# module_decoding_b.net
KiCad netlist of a schematic drawn in EAGLE
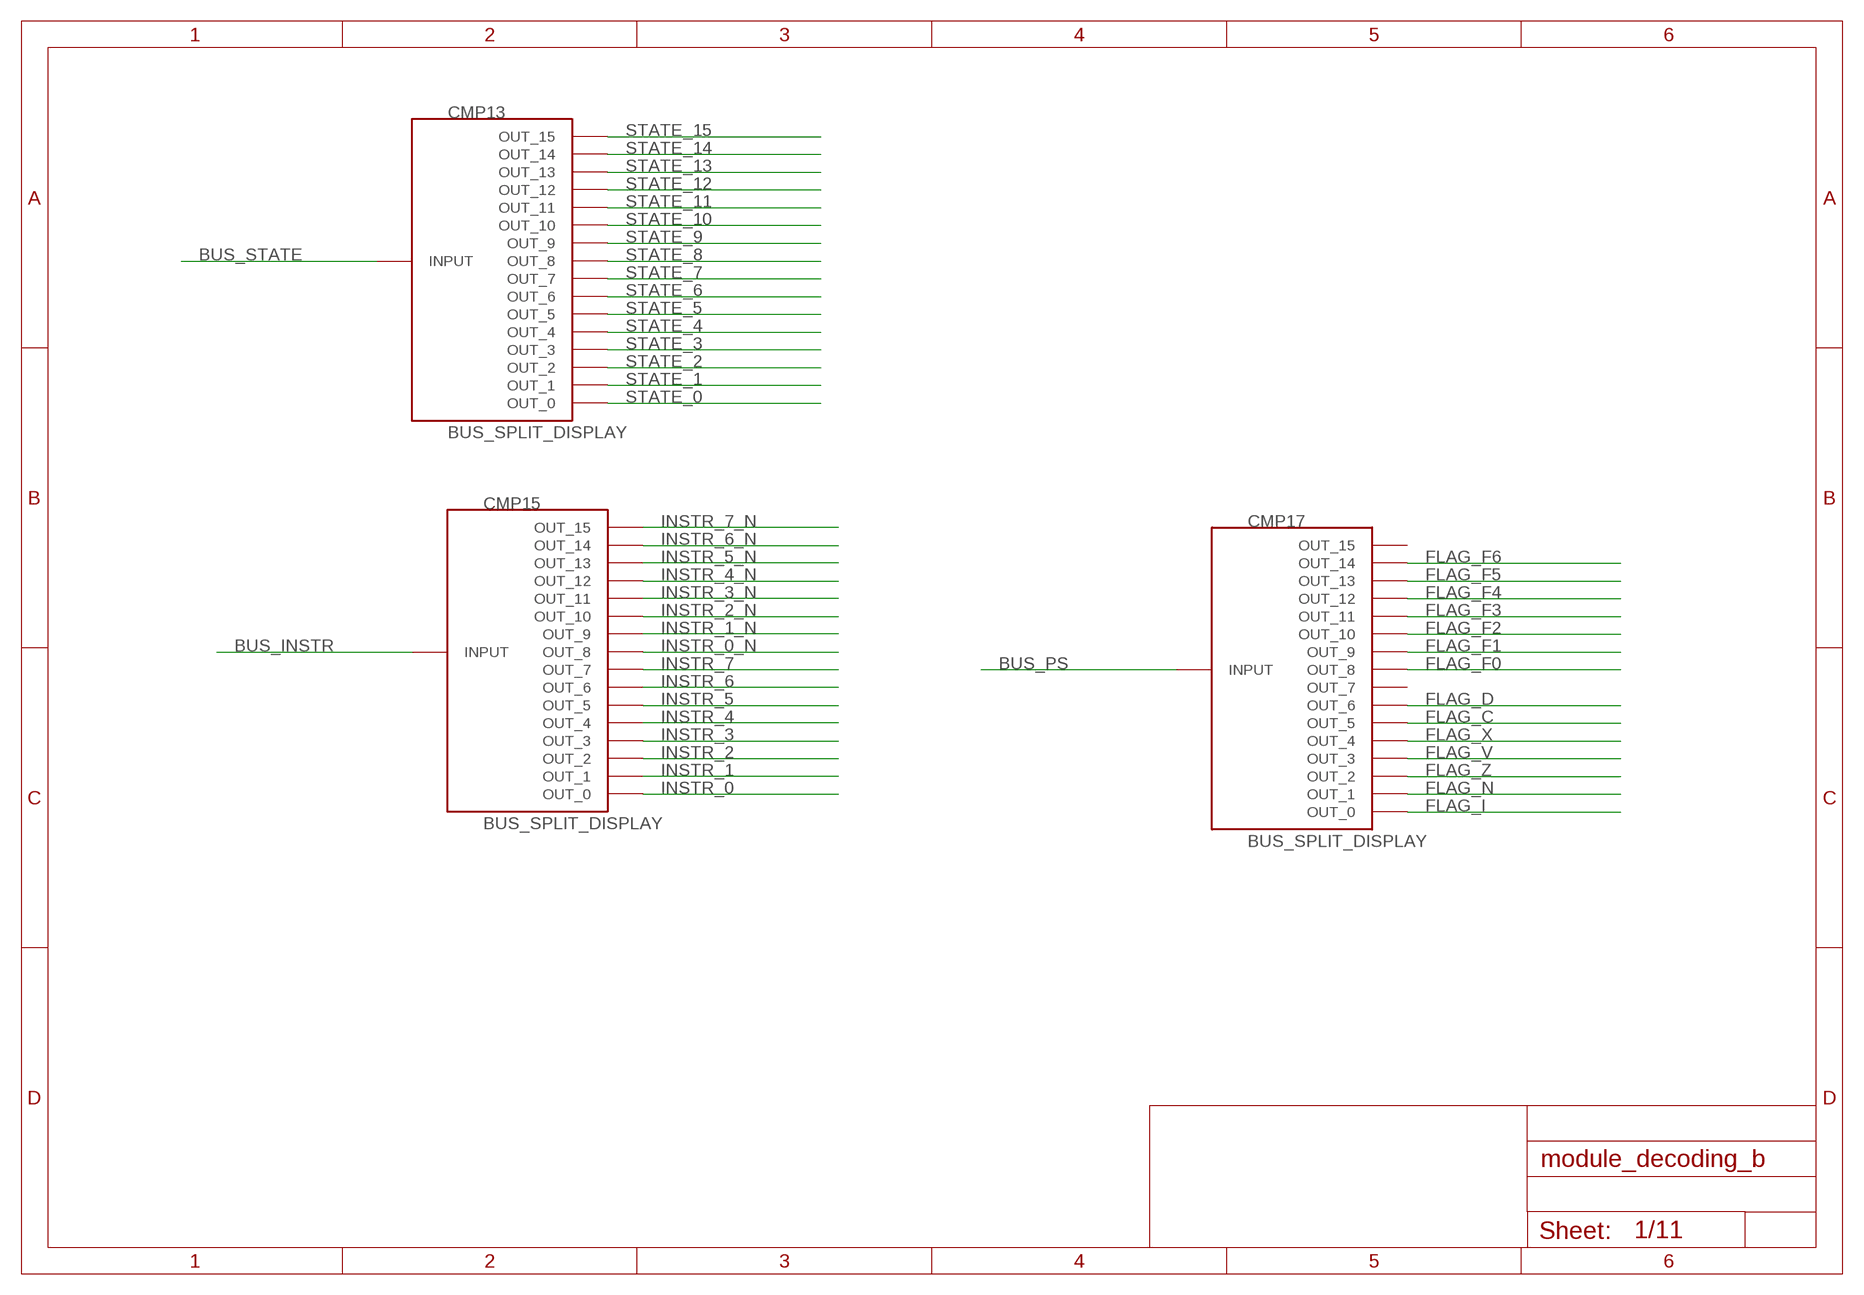
[diagram p0: schematic, sheet 1]
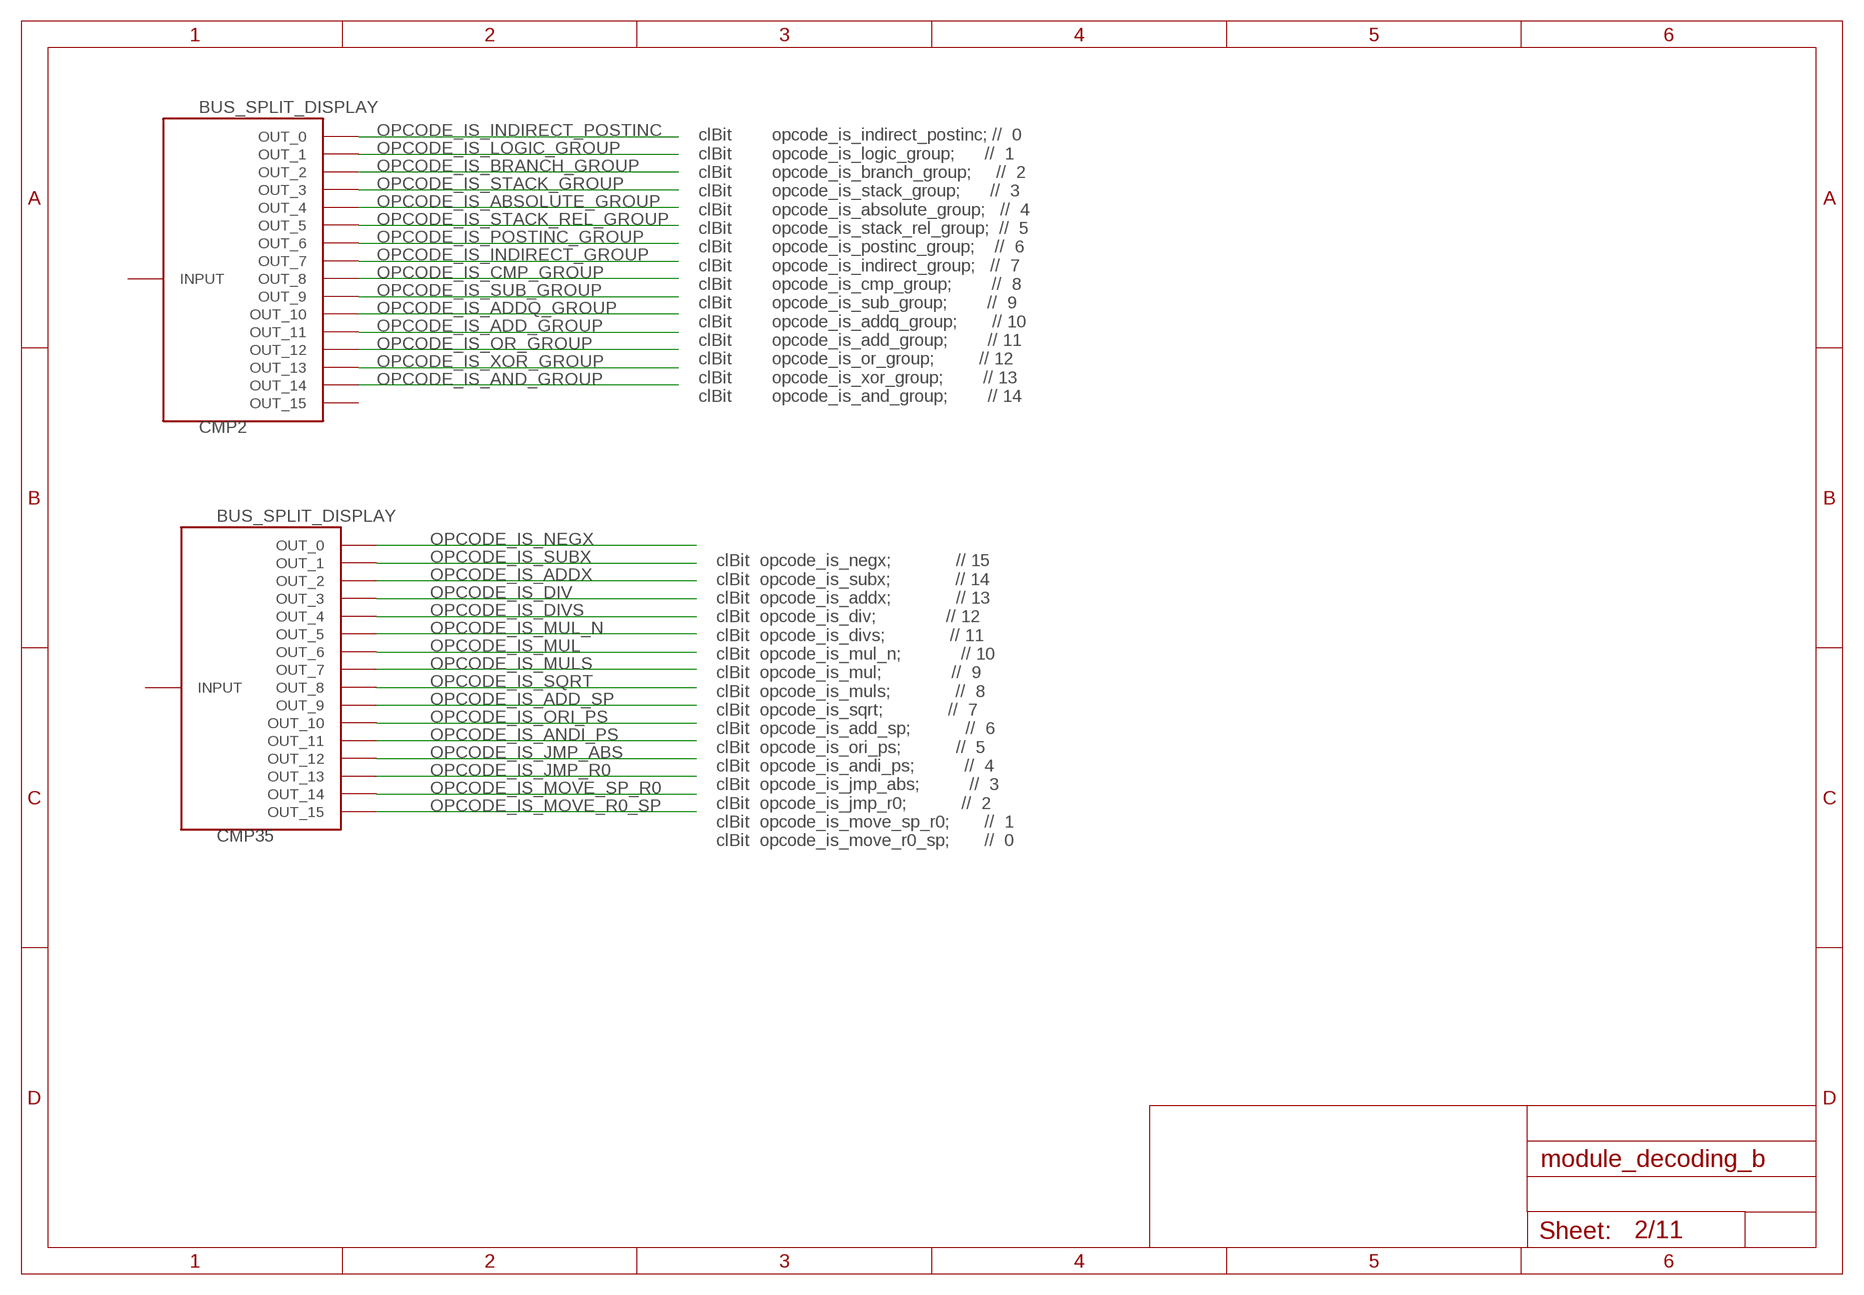
[diagram p1: schematic, sheet 2]
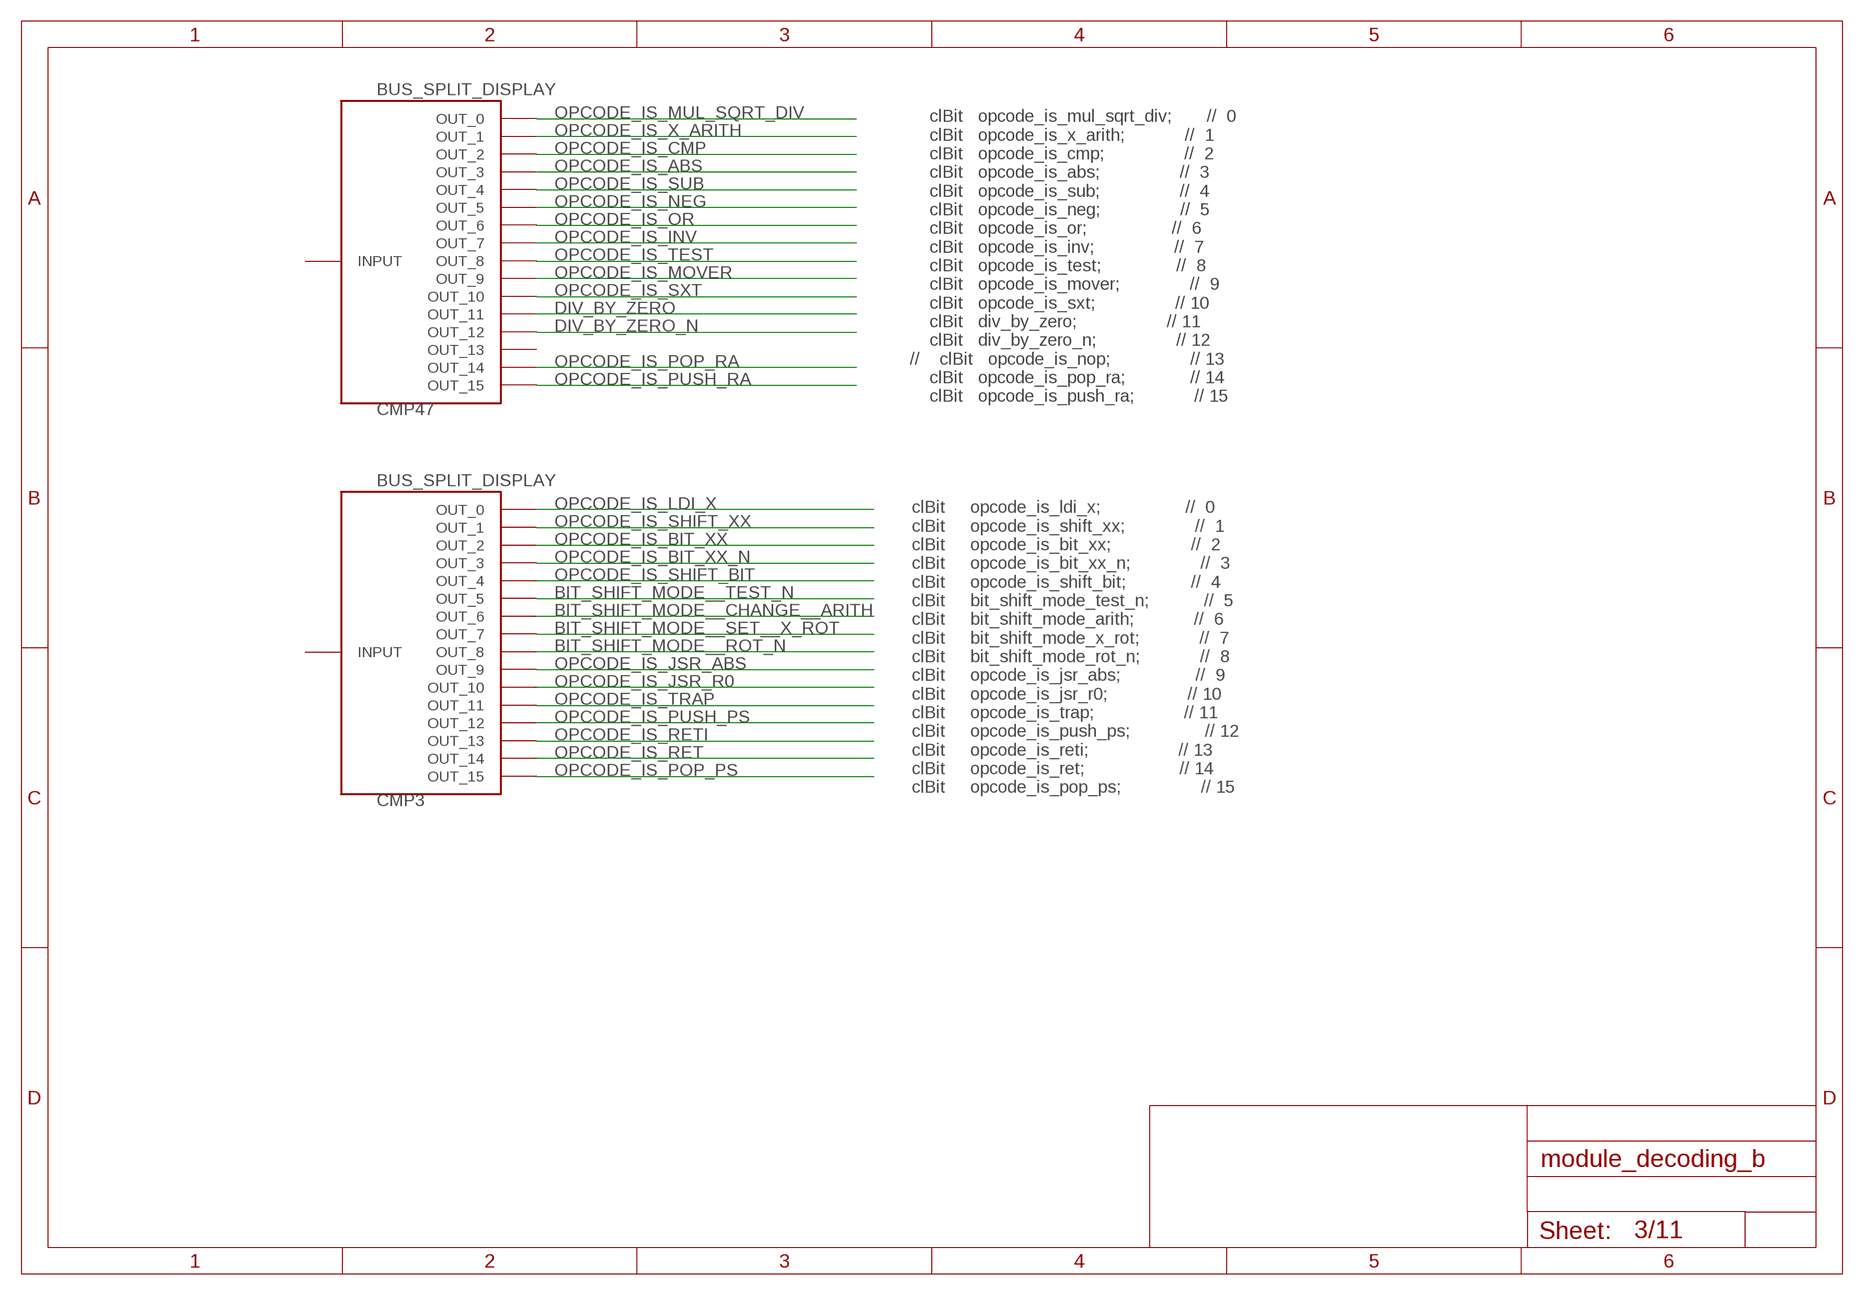
[diagram p2: schematic, sheet 3]
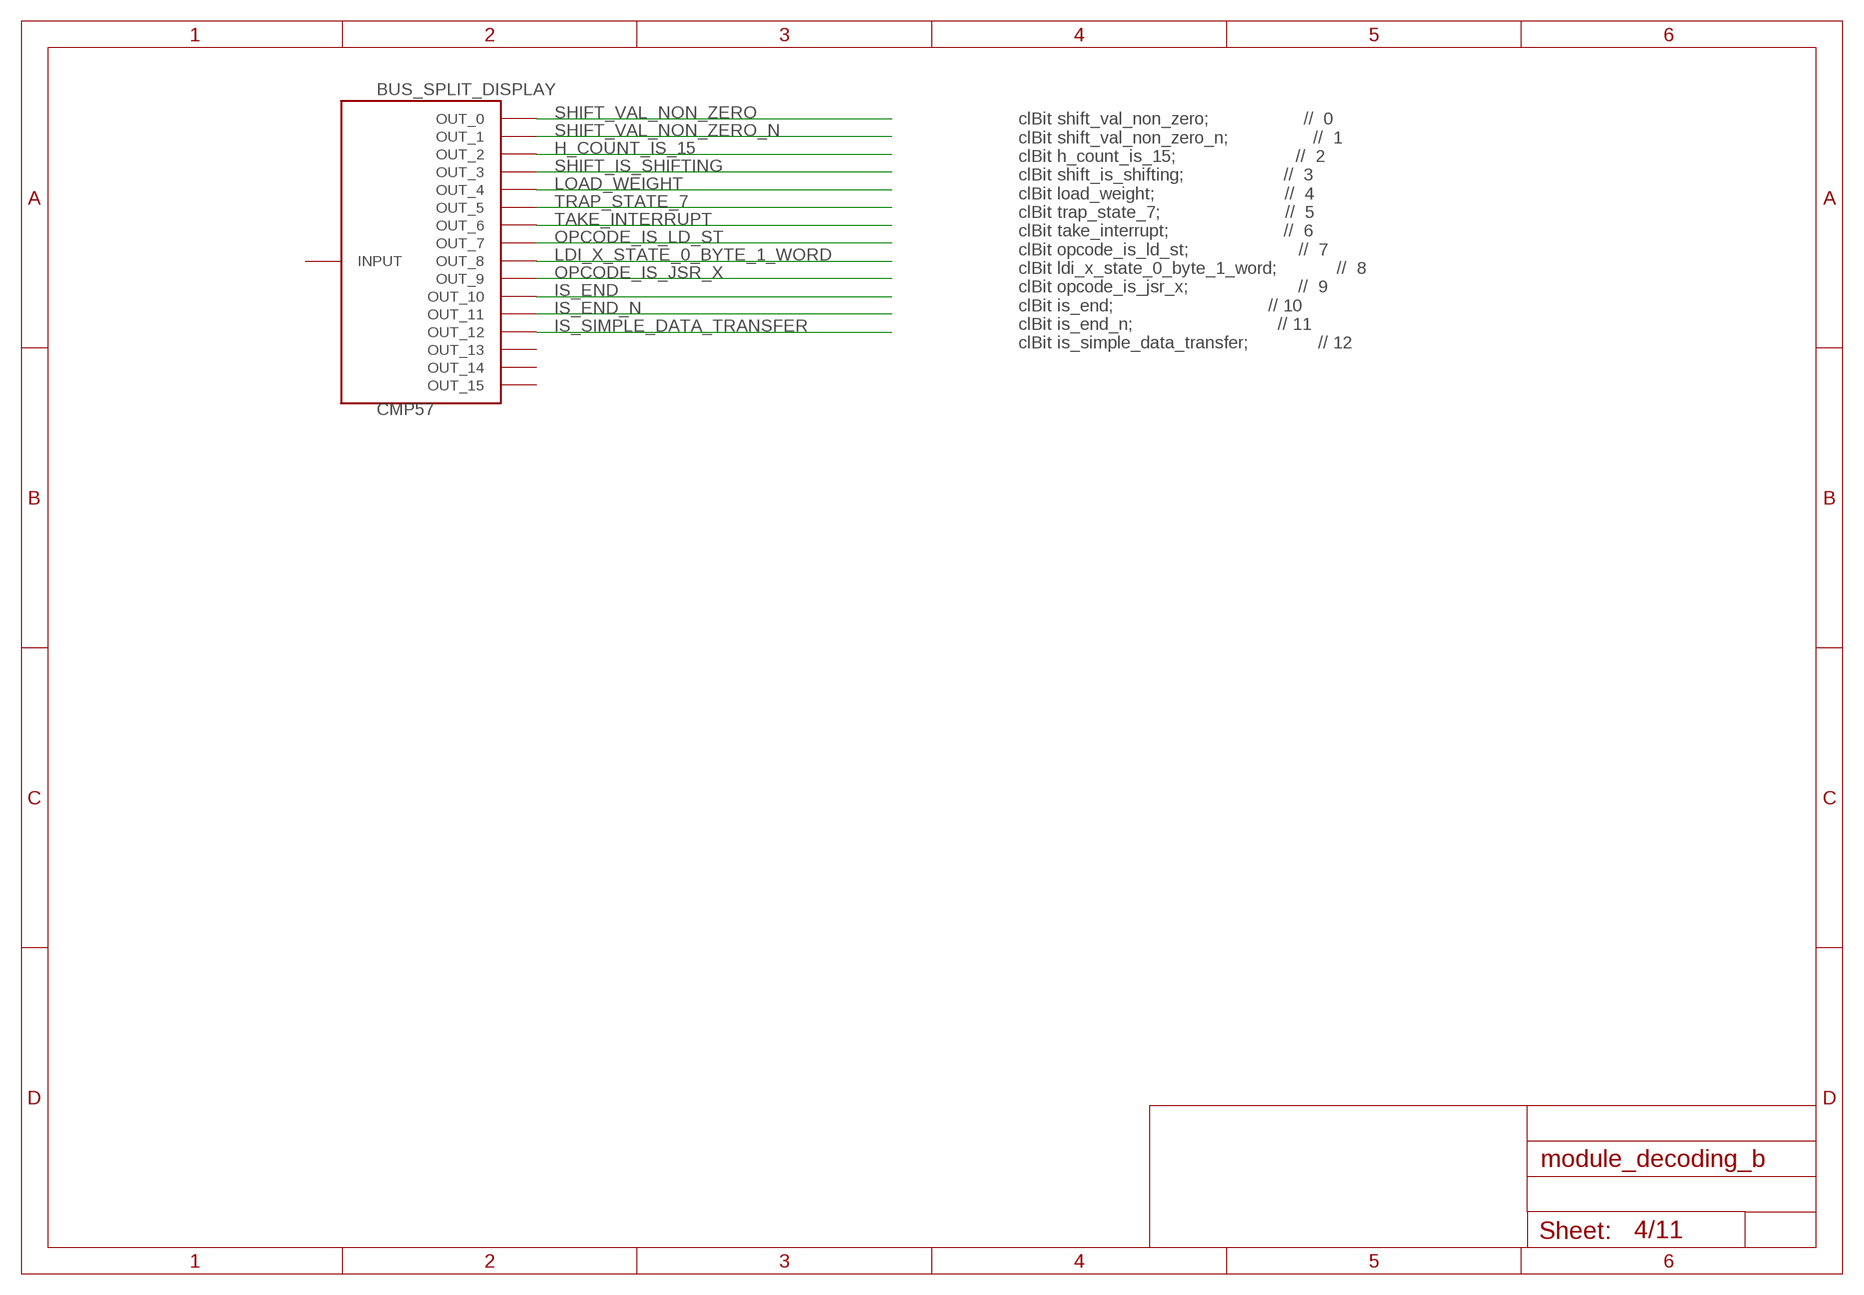
[diagram p3: schematic, sheet 4]
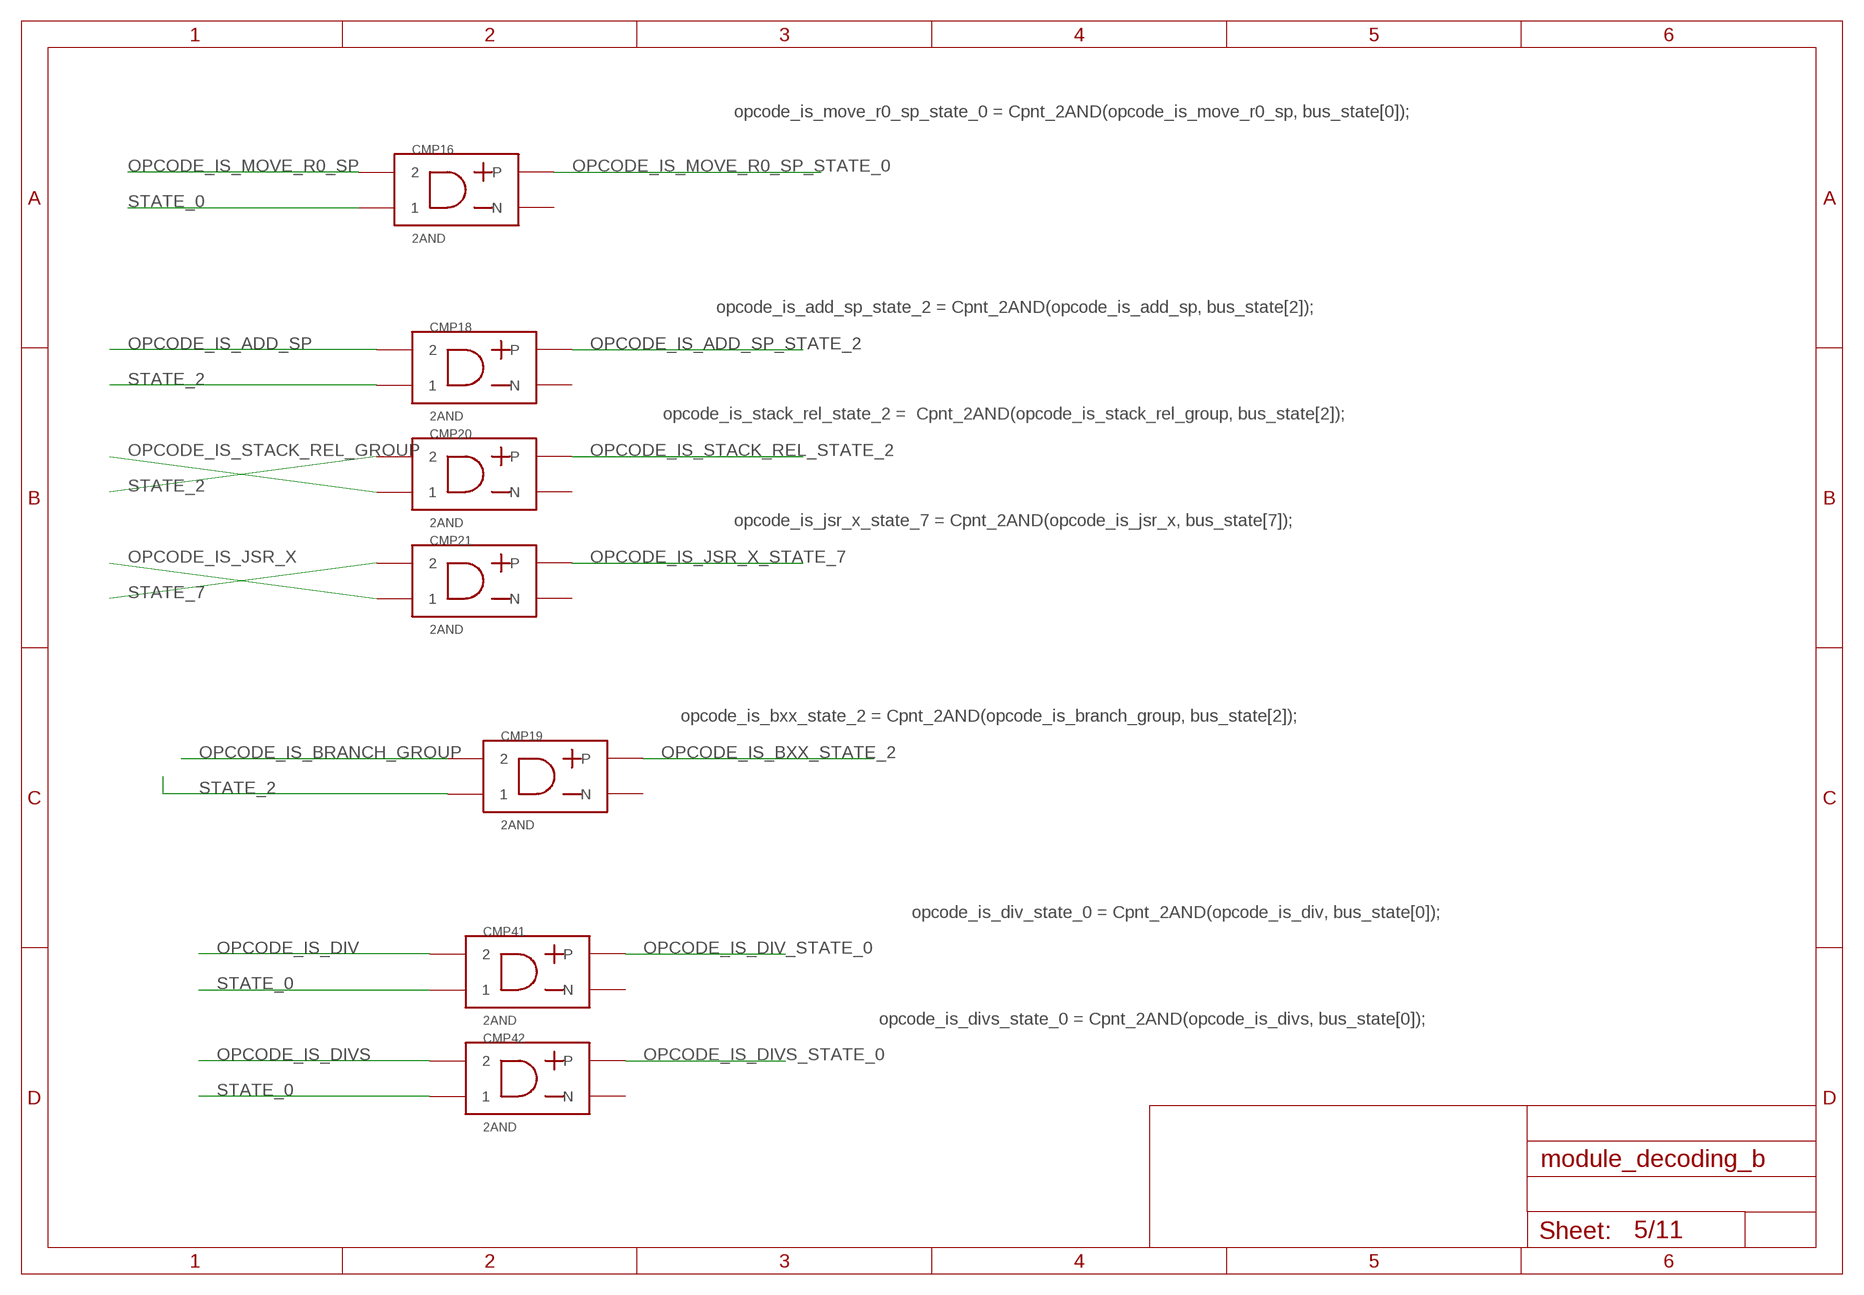
[diagram p4: schematic, sheet 5]
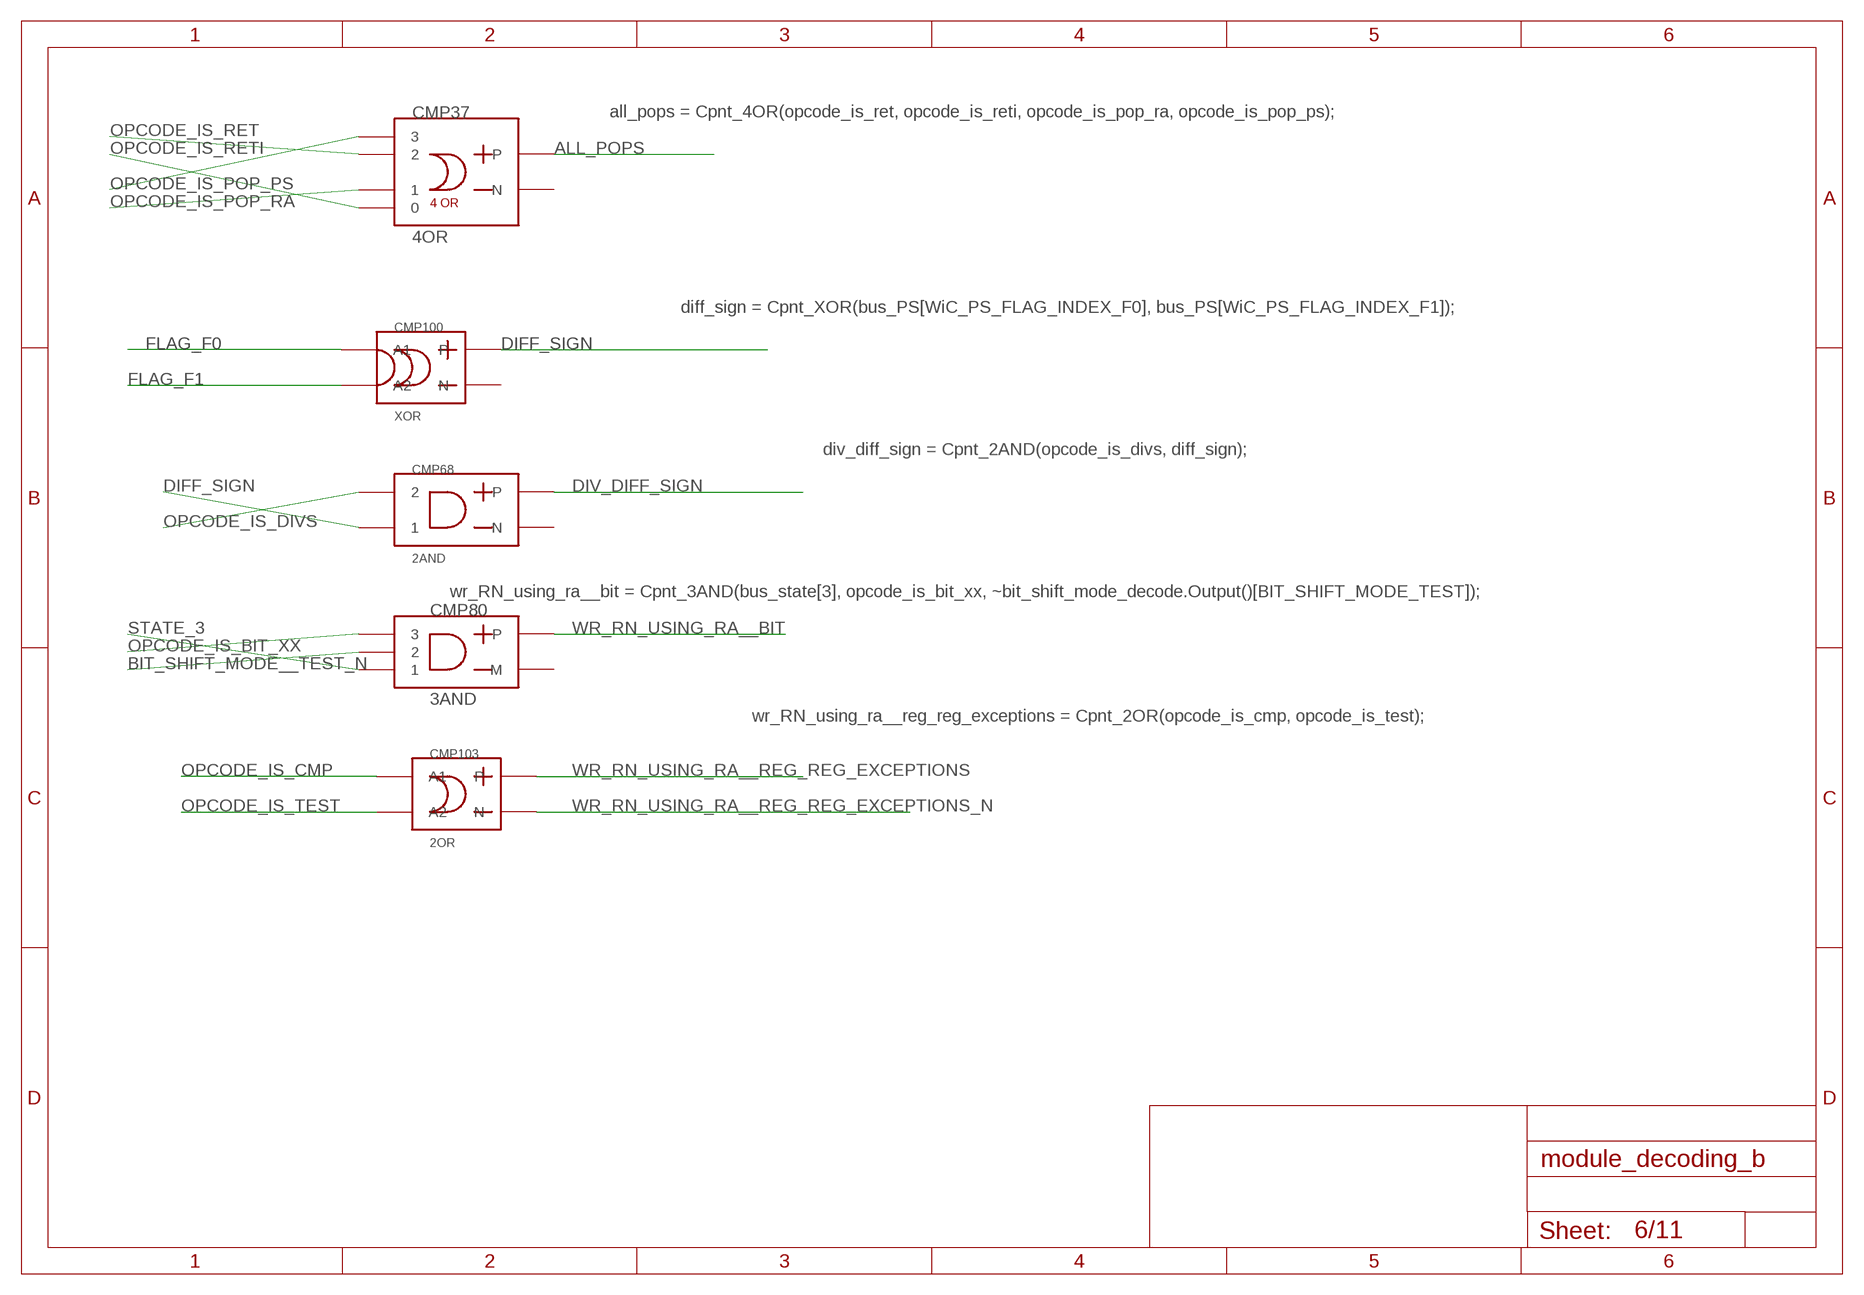
[diagram p5: schematic, sheet 6]
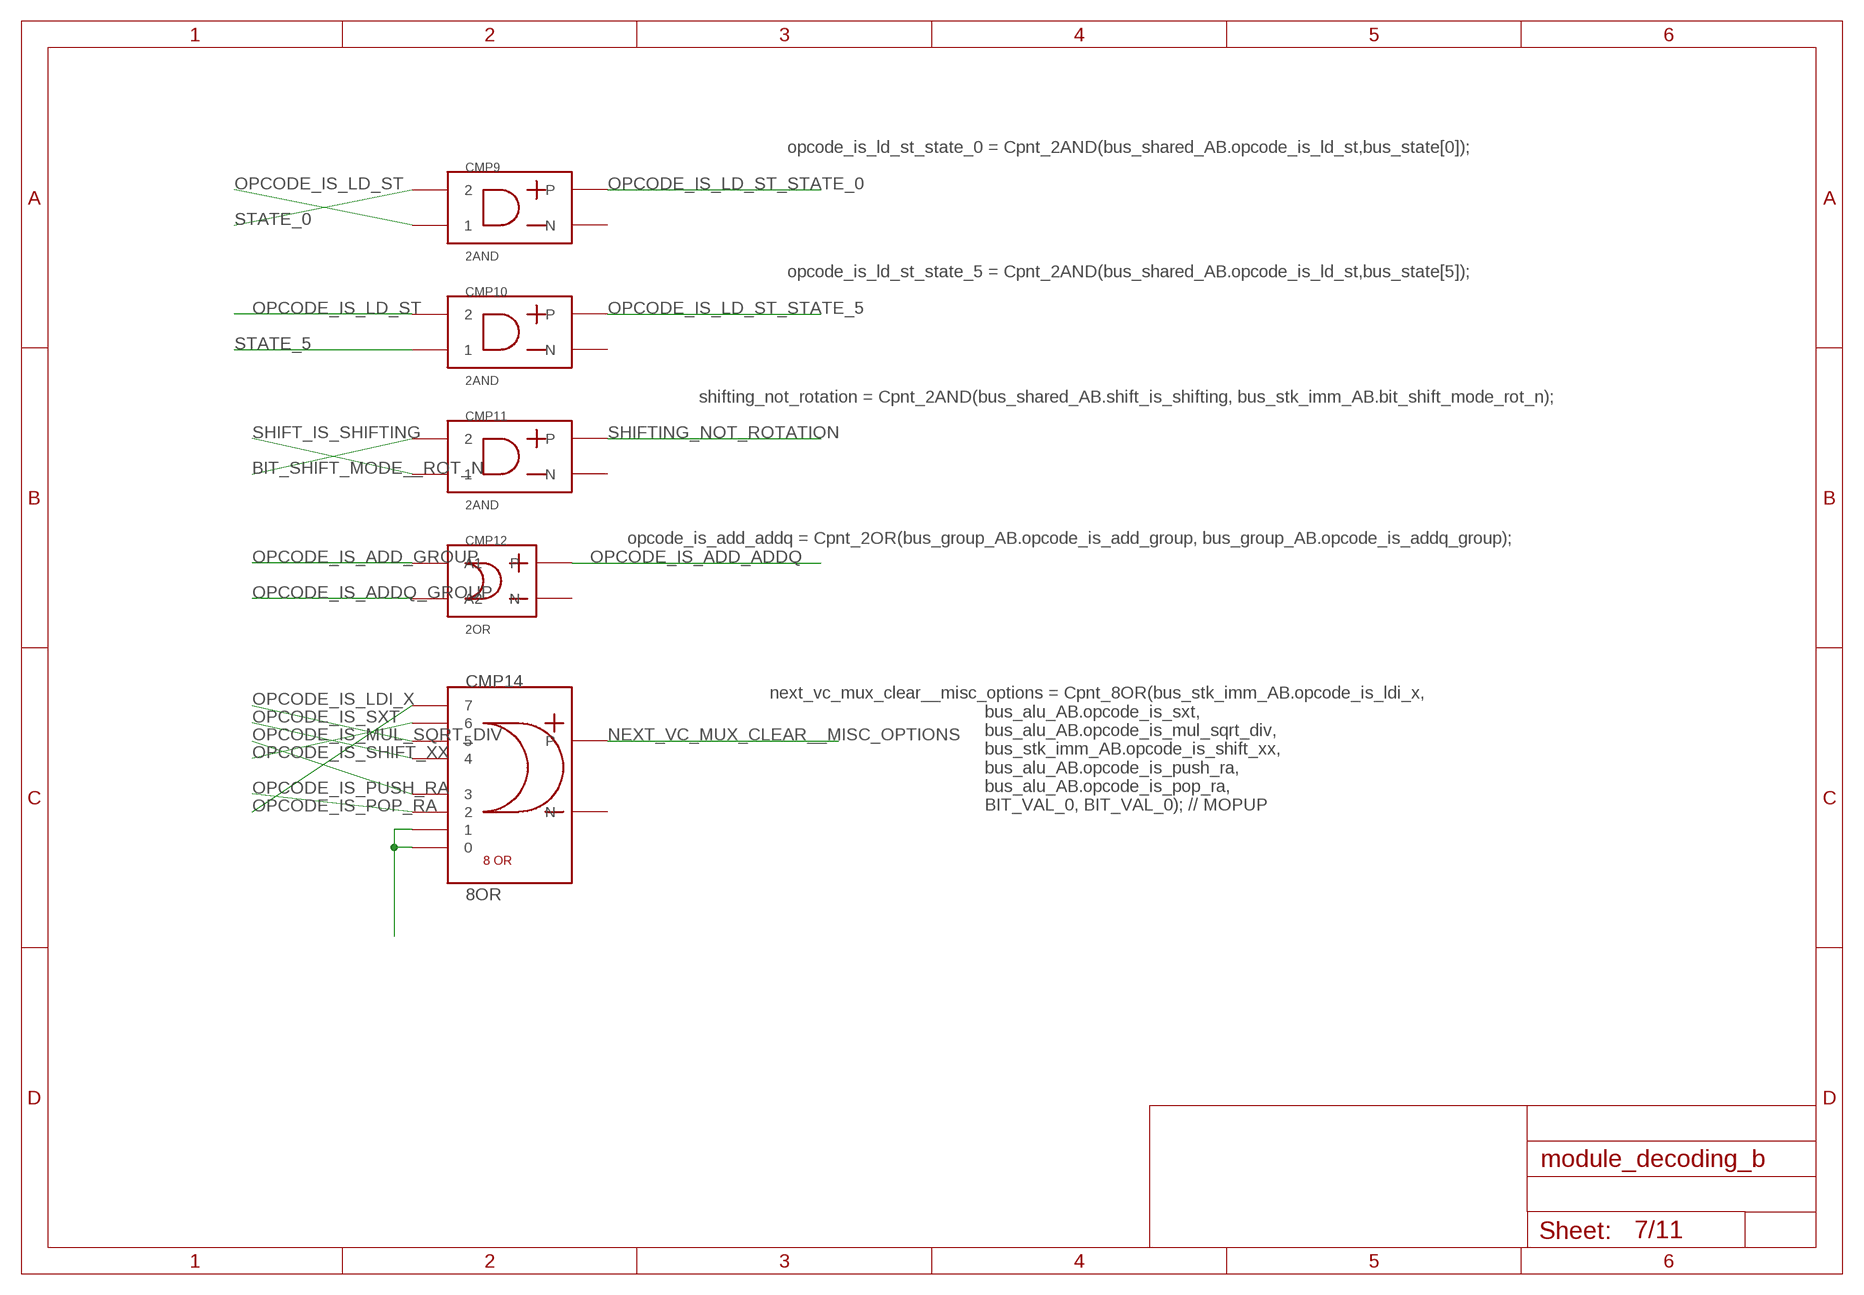
[diagram p6: schematic, sheet 7]
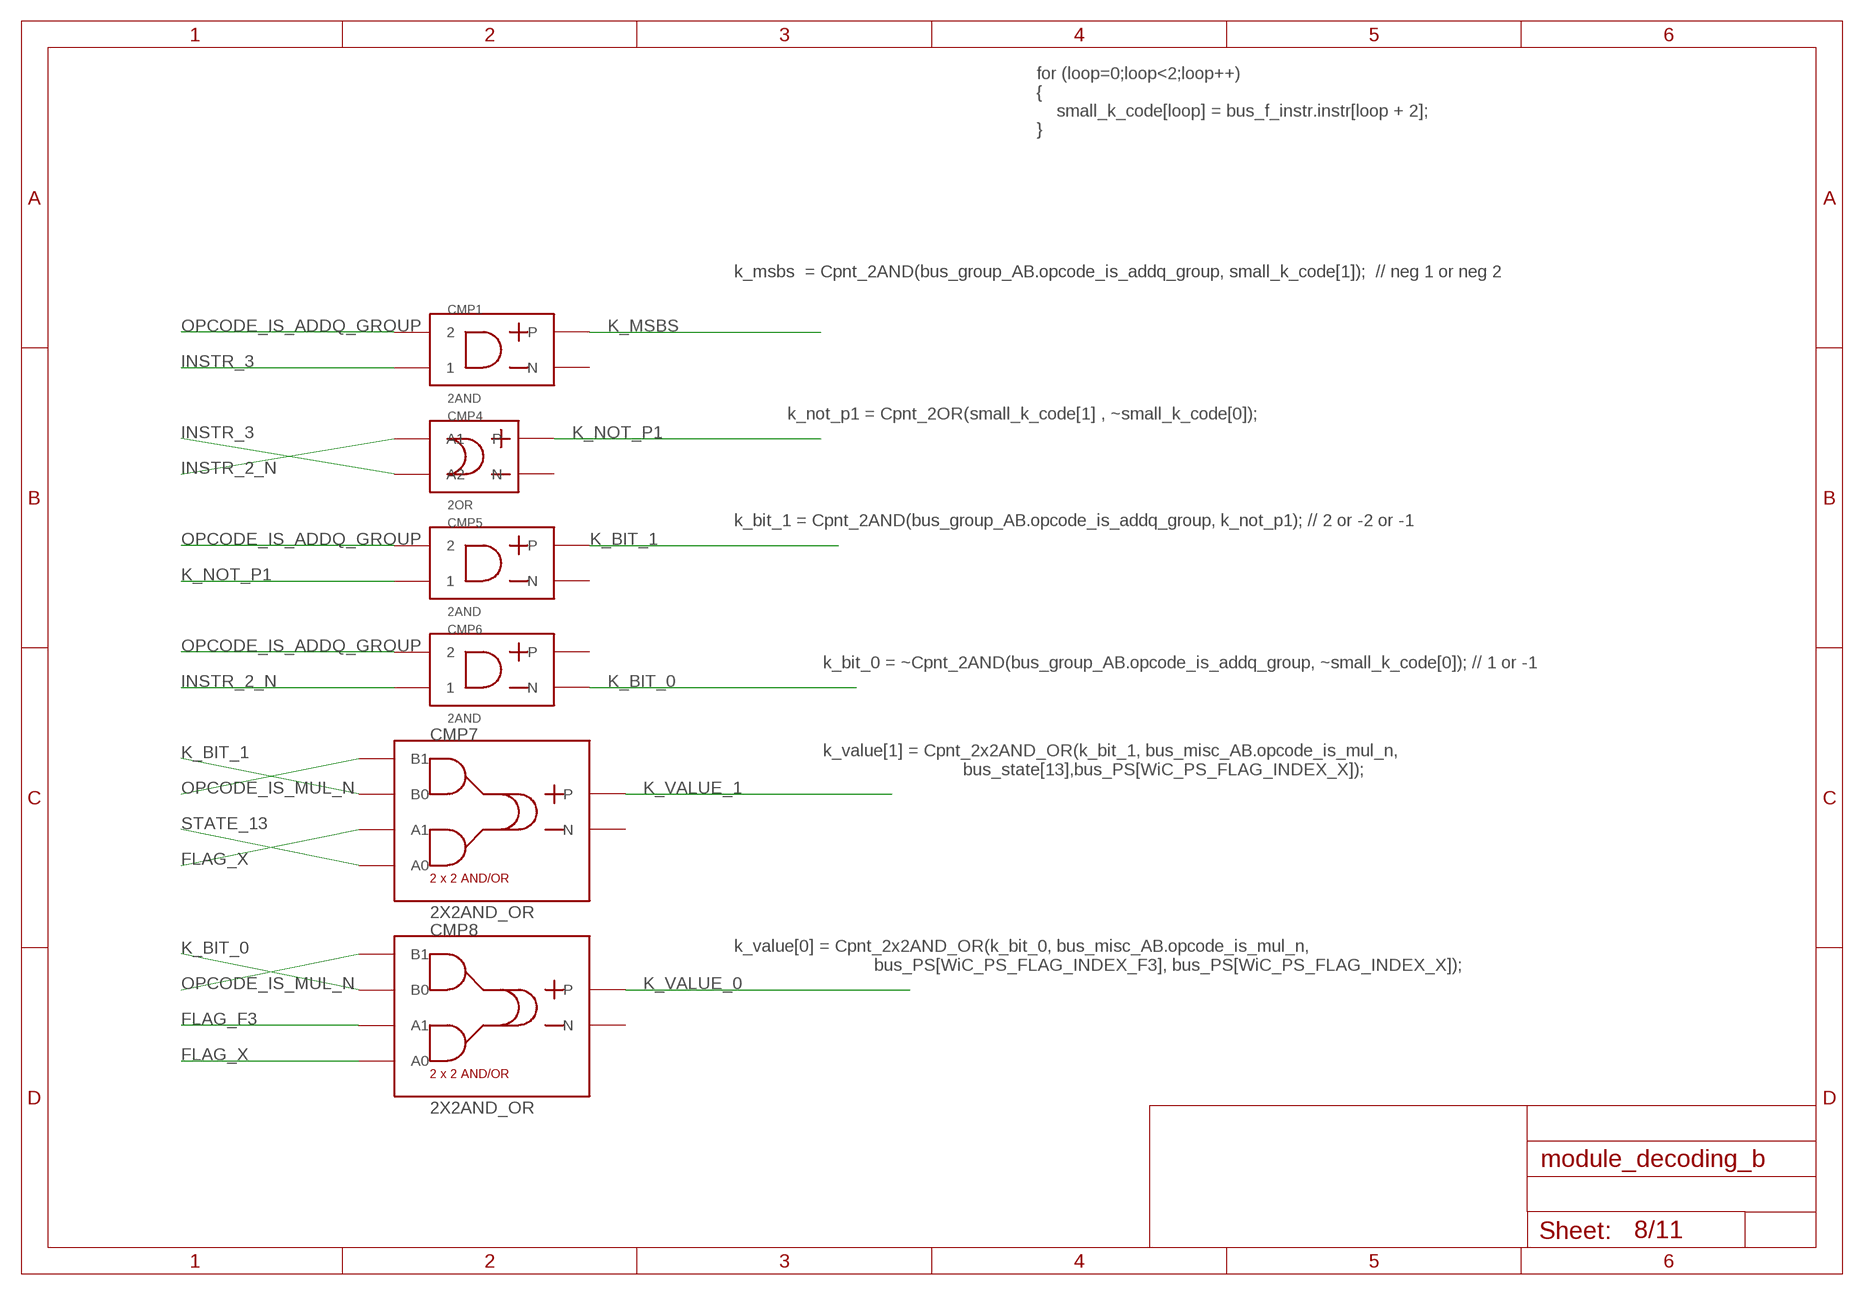
[diagram p7: schematic, sheet 8]
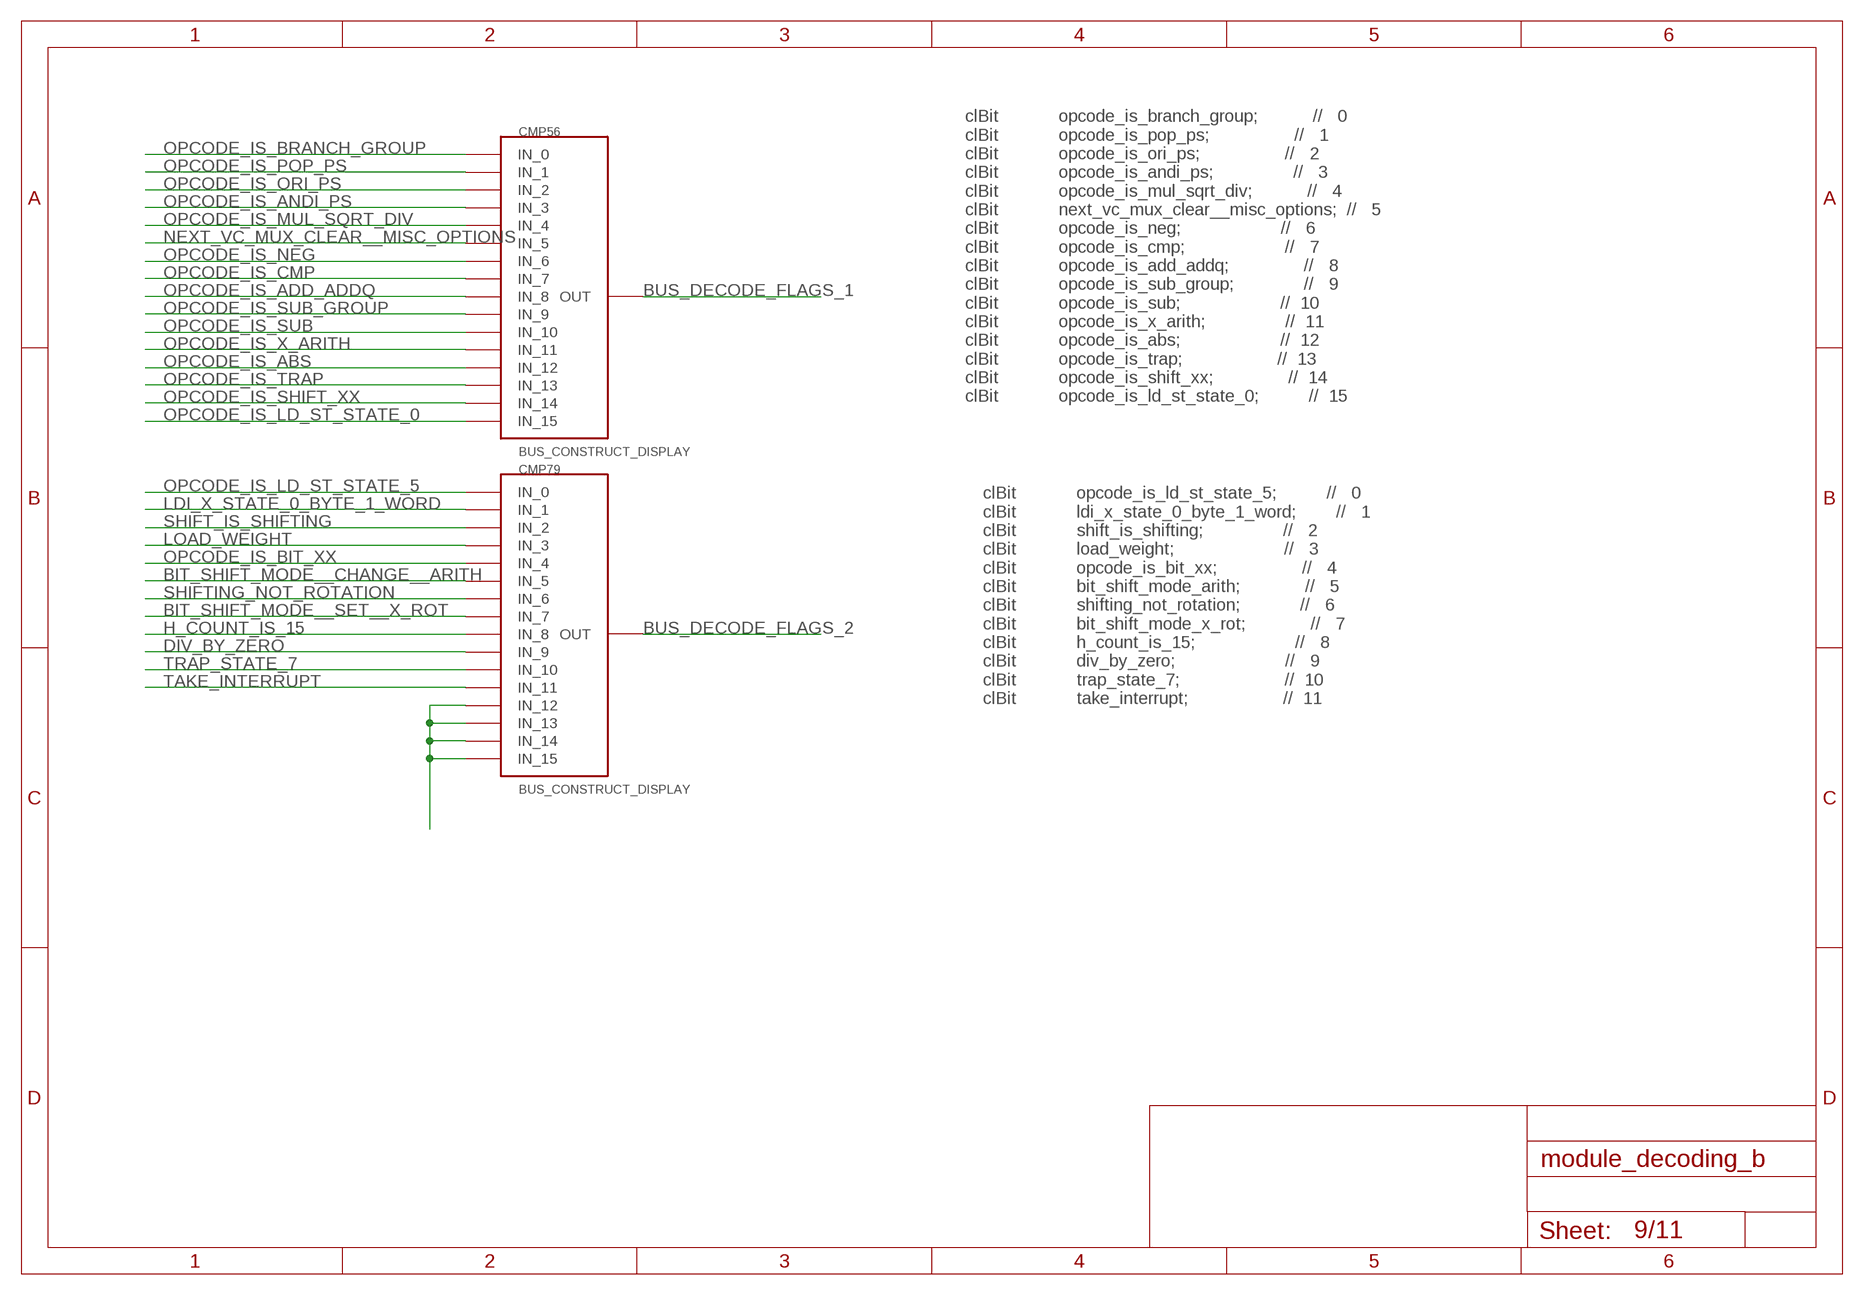
[diagram p8: schematic, sheet 9]
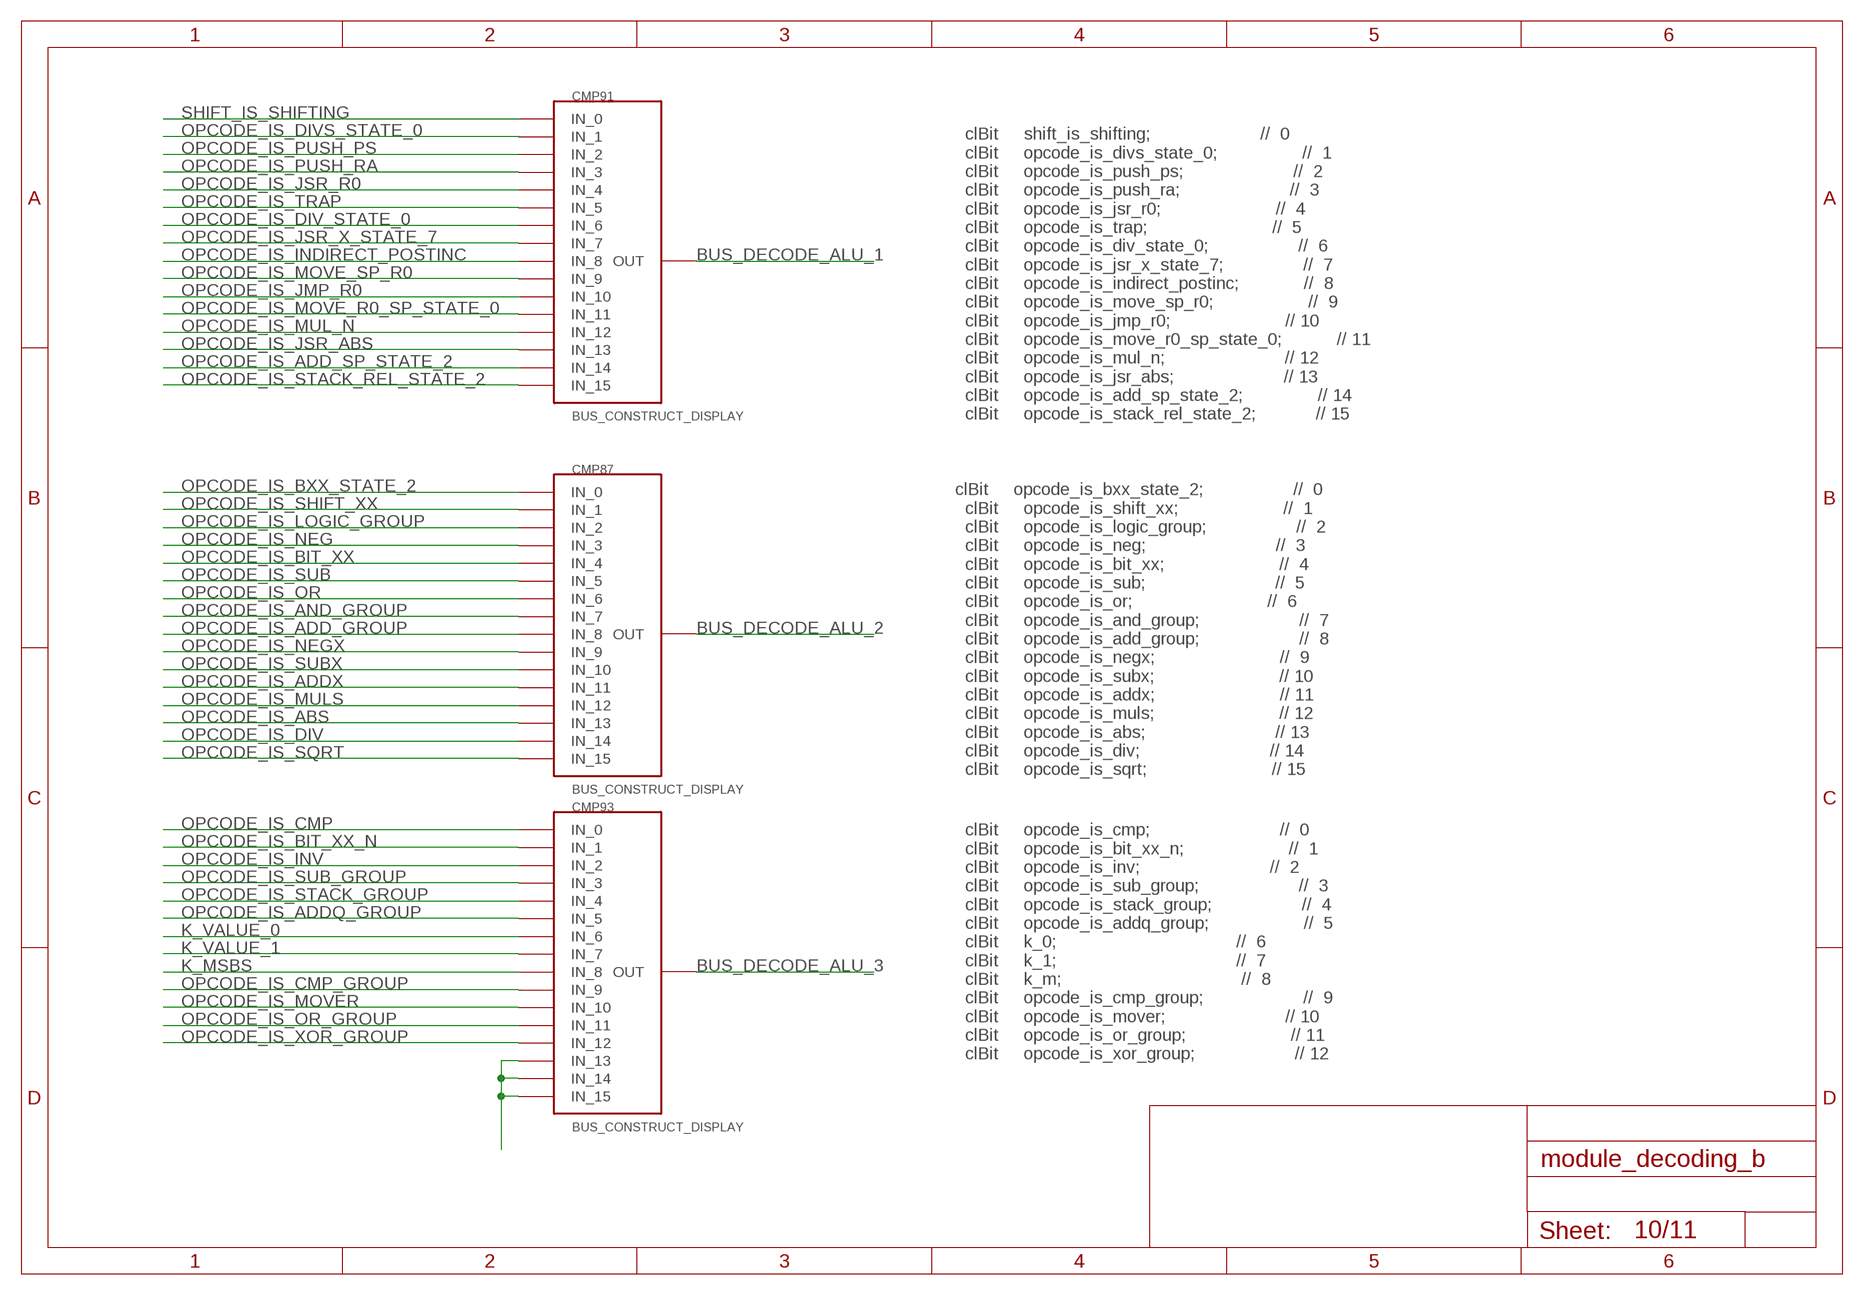
[diagram p9: schematic, sheet 10]
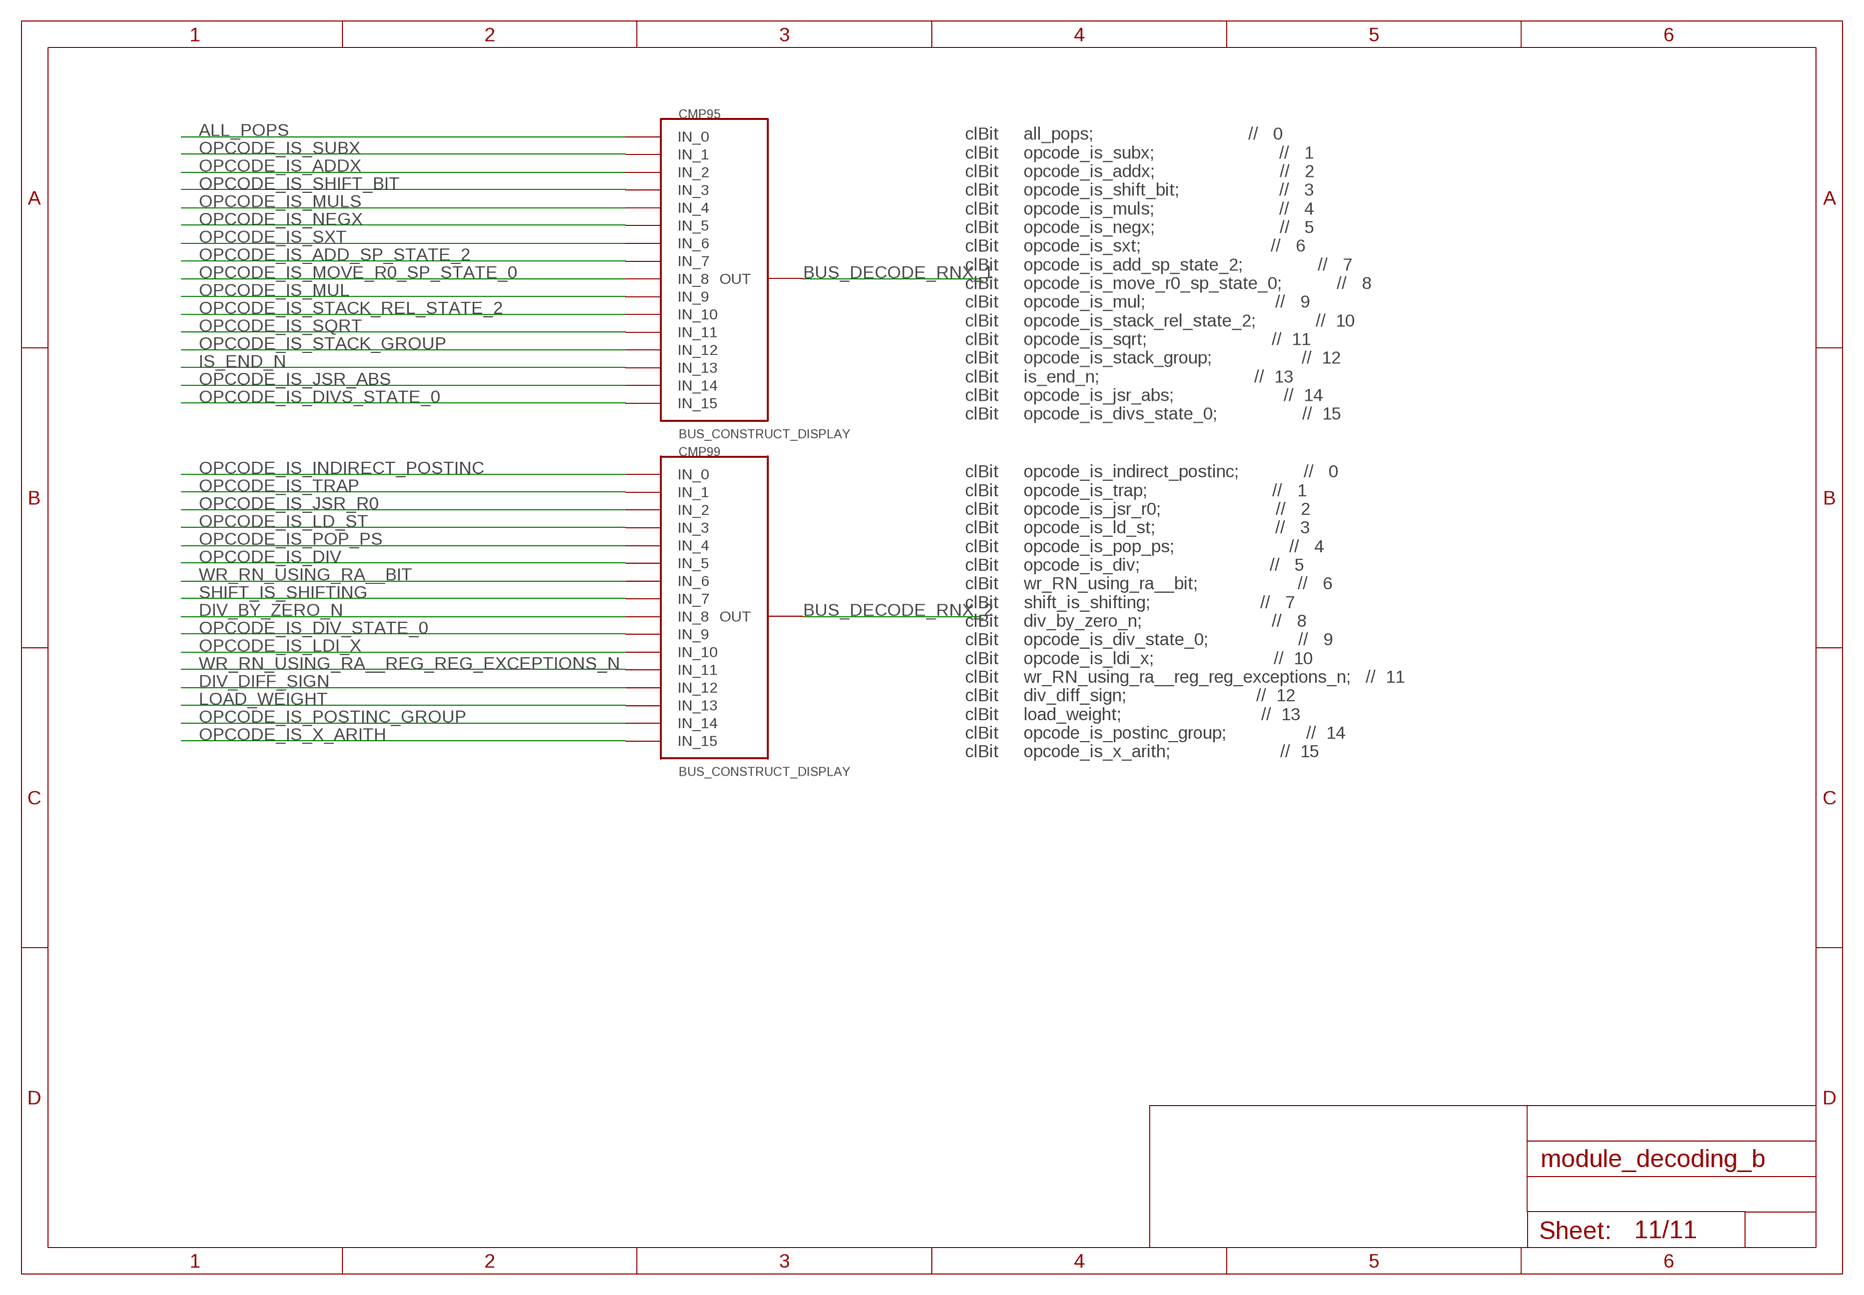
[diagram p10: schematic, sheet 11]

(export (version "E")
  (design (tool "Eeschema 10.0.6"))
  (components
    (comp (ref "CMP56")
      (value "BUS_CONSTRUCT_DISPLAY")
      (footprint "eagle-import:BUS_SPLIT_DISPLAY")
      (libsource (lib "eagle-import") (part "BUS_CONSTRUCT_DISPLAY"))
    )
    (comp (ref "CMP79")
      (value "BUS_CONSTRUCT_DISPLAY")
      (footprint "eagle-import:BUS_SPLIT_DISPLAY")
      (libsource (lib "eagle-import") (part "BUS_CONSTRUCT_DISPLAY"))
    )
    (comp (ref "CMP95")
      (value "BUS_CONSTRUCT_DISPLAY")
      (footprint "eagle-import:BUS_SPLIT_DISPLAY")
      (libsource (lib "eagle-import") (part "BUS_CONSTRUCT_DISPLAY"))
    )
    (comp (ref "CMP99")
      (value "BUS_CONSTRUCT_DISPLAY")
      (footprint "eagle-import:BUS_SPLIT_DISPLAY")
      (libsource (lib "eagle-import") (part "BUS_CONSTRUCT_DISPLAY"))
    )
    (comp (ref "CMP3")
      (value "BUS_SPLIT_DISPLAY")
      (footprint "eagle-import:BUS_SPLIT_DISPLAY")
      (libsource (lib "eagle-import") (part "BUS_SPLIT_DISPLAY"))
    )
    (comp (ref "CMP47")
      (value "BUS_SPLIT_DISPLAY")
      (footprint "eagle-import:BUS_SPLIT_DISPLAY")
      (libsource (lib "eagle-import") (part "BUS_SPLIT_DISPLAY"))
    )
    (comp (ref "CMP87")
      (value "BUS_CONSTRUCT_DISPLAY")
      (footprint "eagle-import:BUS_SPLIT_DISPLAY")
      (libsource (lib "eagle-import") (part "BUS_CONSTRUCT_DISPLAY"))
    )
    (comp (ref "CMP91")
      (value "BUS_CONSTRUCT_DISPLAY")
      (footprint "eagle-import:BUS_SPLIT_DISPLAY")
      (libsource (lib "eagle-import") (part "BUS_CONSTRUCT_DISPLAY"))
    )
    (comp (ref "CMP93")
      (value "BUS_CONSTRUCT_DISPLAY")
      (footprint "eagle-import:BUS_SPLIT_DISPLAY")
      (libsource (lib "eagle-import") (part "BUS_CONSTRUCT_DISPLAY"))
    )
    (comp (ref "CMP1")
      (value "2AND")
      (footprint "eagle-import:2AND")
      (libsource (lib "eagle-import") (part "2AND"))
    )
    (comp (ref "CMP4")
      (value "2OR")
      (footprint "eagle-import:2OR")
      (libsource (lib "eagle-import") (part "2OR"))
    )
    (comp (ref "CMP5")
      (value "2AND")
      (footprint "eagle-import:2AND")
      (libsource (lib "eagle-import") (part "2AND"))
    )
    (comp (ref "CMP6")
      (value "2AND")
      (footprint "eagle-import:2AND")
      (libsource (lib "eagle-import") (part "2AND"))
    )
    (comp (ref "CMP7")
      (value "2X2AND_OR")
      (footprint "eagle-import:2X2AND_OR")
      (libsource (lib "eagle-import") (part "2X2AND_OR"))
    )
    (comp (ref "CMP8")
      (value "2X2AND_OR")
      (footprint "eagle-import:2X2AND_OR")
      (libsource (lib "eagle-import") (part "2X2AND_OR"))
    )
    (comp (ref "CMP57")
      (value "BUS_SPLIT_DISPLAY")
      (footprint "eagle-import:BUS_SPLIT_DISPLAY")
      (libsource (lib "eagle-import") (part "BUS_SPLIT_DISPLAY"))
    )
    (comp (ref "CMP37")
      (value "4OR")
      (footprint "eagle-import:4OR")
      (libsource (lib "eagle-import") (part "4OR"))
    )
    (comp (ref "CMP68")
      (value "2AND")
      (footprint "eagle-import:2AND")
      (libsource (lib "eagle-import") (part "2AND"))
    )
    (comp (ref "CMP80")
      (value "3AND")
      (footprint "eagle-import:3AND")
      (libsource (lib "eagle-import") (part "3AND"))
    )
    (comp (ref "CMP100")
      (value "XOR")
      (footprint "eagle-import:XOR")
      (libsource (lib "eagle-import") (part "XOR"))
    )
    (comp (ref "CMP103")
      (value "2OR")
      (footprint "eagle-import:2OR")
      (libsource (lib "eagle-import") (part "2OR"))
    )
    (comp (ref "CMP2")
      (value "BUS_SPLIT_DISPLAY")
      (footprint "eagle-import:BUS_SPLIT_DISPLAY")
      (libsource (lib "eagle-import") (part "BUS_SPLIT_DISPLAY"))
    )
    (comp (ref "CMP35")
      (value "BUS_SPLIT_DISPLAY")
      (footprint "eagle-import:BUS_SPLIT_DISPLAY")
      (libsource (lib "eagle-import") (part "BUS_SPLIT_DISPLAY"))
    )
    (comp (ref "CMP9")
      (value "2AND")
      (footprint "eagle-import:2AND")
      (libsource (lib "eagle-import") (part "2AND"))
    )
    (comp (ref "CMP10")
      (value "2AND")
      (footprint "eagle-import:2AND")
      (libsource (lib "eagle-import") (part "2AND"))
    )
    (comp (ref "CMP11")
      (value "2AND")
      (footprint "eagle-import:2AND")
      (libsource (lib "eagle-import") (part "2AND"))
    )
    (comp (ref "CMP12")
      (value "2OR")
      (footprint "eagle-import:2OR")
      (libsource (lib "eagle-import") (part "2OR"))
    )
    (comp (ref "CMP14")
      (value "8OR")
      (footprint "eagle-import:8OR")
      (libsource (lib "eagle-import") (part "8OR"))
    )
    (comp (ref "CMP13")
      (value "BUS_SPLIT_DISPLAY")
      (footprint "eagle-import:BUS_SPLIT_DISPLAY")
      (libsource (lib "eagle-import") (part "BUS_SPLIT_DISPLAY"))
    )
    (comp (ref "CMP15")
      (value "BUS_SPLIT_DISPLAY")
      (footprint "eagle-import:BUS_SPLIT_DISPLAY")
      (libsource (lib "eagle-import") (part "BUS_SPLIT_DISPLAY"))
    )
    (comp (ref "CMP17")
      (value "BUS_SPLIT_DISPLAY")
      (footprint "eagle-import:BUS_SPLIT_DISPLAY")
      (libsource (lib "eagle-import") (part "BUS_SPLIT_DISPLAY"))
    )
    (comp (ref "CMP16")
      (value "2AND")
      (footprint "eagle-import:2AND")
      (libsource (lib "eagle-import") (part "2AND"))
    )
    (comp (ref "CMP18")
      (value "2AND")
      (footprint "eagle-import:2AND")
      (libsource (lib "eagle-import") (part "2AND"))
    )
    (comp (ref "CMP19")
      (value "2AND")
      (footprint "eagle-import:2AND")
      (libsource (lib "eagle-import") (part "2AND"))
    )
    (comp (ref "CMP20")
      (value "2AND")
      (footprint "eagle-import:2AND")
      (libsource (lib "eagle-import") (part "2AND"))
    )
    (comp (ref "CMP21")
      (value "2AND")
      (footprint "eagle-import:2AND")
      (libsource (lib "eagle-import") (part "2AND"))
    )
    (comp (ref "CMP41")
      (value "2AND")
      (footprint "eagle-import:2AND")
      (libsource (lib "eagle-import") (part "2AND"))
    )
    (comp (ref "CMP42")
      (value "2AND")
      (footprint "eagle-import:2AND")
      (libsource (lib "eagle-import") (part "2AND"))
    )
  )
  (nets
    (net (code "1") (name "ALL_POPS") (class "Default")
      (node (ref "CMP37") (pin "OUT_P") (pinfunction "P_OUT_P") (pintype "output"))
      (node (ref "CMP95") (pin "P$1") (pinfunction "IN_0_P$1") (pintype "input"))
    )
    (net (code "2") (name "BIT_SHIFT_MODE__CHANGE__ARITH") (class "Default")
      (node (ref "CMP3") (pin "P$7") (pinfunction "OUT_6_P$7") (pintype "output"))
      (node (ref "CMP79") (pin "P$6") (pinfunction "IN_5_P$6") (pintype "input"))
    )
    (net (code "3") (name "BIT_SHIFT_MODE__ROT_N") (class "Default")
      (node (ref "CMP11") (pin "P$2") (pinfunction "2_P$2") (pintype "input"))
      (node (ref "CMP3") (pin "P$9") (pinfunction "OUT_8_P$9") (pintype "output"))
    )
    (net (code "4") (name "BIT_SHIFT_MODE__SET__X_ROT") (class "Default")
      (node (ref "CMP3") (pin "P$8") (pinfunction "OUT_7_P$8") (pintype "output"))
      (node (ref "CMP79") (pin "P$8") (pinfunction "IN_7_P$8") (pintype "input"))
    )
    (net (code "5") (name "BIT_SHIFT_MODE__TEST_N") (class "Default")
      (node (ref "CMP3") (pin "P$6") (pinfunction "OUT_5_P$6") (pintype "output"))
      (node (ref "CMP80") (pin "P$2") (pinfunction "2_P$2") (pintype "input"))
    )
    (net (code "6") (name "BUS_DECODE_ALU_1") (class "Default")
      (node (ref "CMP91") (pin "INPUT") (pinfunction "OUT_INPUT") (pintype "output"))
    )
    (net (code "7") (name "BUS_DECODE_ALU_2") (class "Default")
      (node (ref "CMP87") (pin "INPUT") (pinfunction "OUT_INPUT") (pintype "output"))
    )
    (net (code "8") (name "BUS_DECODE_ALU_3") (class "Default")
      (node (ref "CMP93") (pin "INPUT") (pinfunction "OUT_INPUT") (pintype "output"))
    )
    (net (code "9") (name "BUS_DECODE_FLAGS_1") (class "Default")
      (node (ref "CMP56") (pin "INPUT") (pinfunction "OUT_INPUT") (pintype "output"))
    )
    (net (code "10") (name "BUS_DECODE_FLAGS_2") (class "Default")
      (node (ref "CMP79") (pin "INPUT") (pinfunction "OUT_INPUT") (pintype "output"))
    )
    (net (code "11") (name "BUS_DECODE_RNX_1") (class "Default")
      (node (ref "CMP95") (pin "INPUT") (pinfunction "OUT_INPUT") (pintype "output"))
    )
    (net (code "12") (name "BUS_DECODE_RNX_2") (class "Default")
      (node (ref "CMP99") (pin "INPUT") (pinfunction "OUT_INPUT") (pintype "output"))
    )
    (net (code "13") (name "BUS_INSTR") (class "Default")
      (node (ref "CMP15") (pin "INPUT") (pinfunction "INPUT_INPUT") (pintype "input"))
    )
    (net (code "14") (name "BUS_PS") (class "Default")
      (node (ref "CMP17") (pin "INPUT") (pinfunction "INPUT_INPUT") (pintype "input"))
    )
    (net (code "15") (name "BUS_STATE") (class "Default")
      (node (ref "CMP13") (pin "INPUT") (pinfunction "INPUT_INPUT") (pintype "input"))
    )
    (net (code "16") (name "DIFF_SIGN") (class "Default")
      (node (ref "CMP100") (pin "OUT_P") (pinfunction "P_OUT_P") (pintype "output"))
      (node (ref "CMP68") (pin "P$1") (pinfunction "1_P$1") (pintype "input"))
    )
    (net (code "17") (name "DIV_BY_ZERO") (class "Default")
      (node (ref "CMP47") (pin "P$12") (pinfunction "OUT_11_P$12") (pintype "output"))
      (node (ref "CMP79") (pin "P$10") (pinfunction "IN_9_P$10") (pintype "input"))
    )
    (net (code "18") (name "DIV_BY_ZERO_N") (class "Default")
      (node (ref "CMP47") (pin "P$13") (pinfunction "OUT_12_P$13") (pintype "output"))
      (node (ref "CMP99") (pin "P$9") (pinfunction "IN_8_P$9") (pintype "input"))
    )
    (net (code "19") (name "DIV_DIFF_SIGN") (class "Default")
      (node (ref "CMP68") (pin "OUT_P") (pinfunction "P_OUT_P") (pintype "output"))
      (node (ref "CMP99") (pin "P$13") (pinfunction "IN_12_P$13") (pintype "input"))
    )
    (net (code "20") (name "FLAG_C") (class "Default")
      (node (ref "CMP17") (pin "P$6") (pinfunction "OUT_5_P$6") (pintype "output"))
    )
    (net (code "21") (name "FLAG_D") (class "Default")
      (node (ref "CMP17") (pin "P$7") (pinfunction "OUT_6_P$7") (pintype "output"))
    )
    (net (code "22") (name "FLAG_F0") (class "Default")
      (node (ref "CMP100") (pin "P$1") (pinfunction "A1_P$1") (pintype "input"))
      (node (ref "CMP17") (pin "P$9") (pinfunction "OUT_8_P$9") (pintype "output"))
    )
    (net (code "23") (name "FLAG_F1") (class "Default")
      (node (ref "CMP100") (pin "P$2") (pinfunction "A2_P$2") (pintype "input"))
      (node (ref "CMP17") (pin "P$10") (pinfunction "OUT_9_P$10") (pintype "output"))
    )
    (net (code "24") (name "FLAG_F2") (class "Default")
      (node (ref "CMP17") (pin "P$11") (pinfunction "OUT_10_P$11") (pintype "output"))
    )
    (net (code "25") (name "FLAG_F3") (class "Default")
      (node (ref "CMP17") (pin "P$12") (pinfunction "OUT_11_P$12") (pintype "output"))
      (node (ref "CMP8") (pin "P$2") (pinfunction "A1_P$2") (pintype "input"))
    )
    (net (code "26") (name "FLAG_F4") (class "Default")
      (node (ref "CMP17") (pin "P$13") (pinfunction "OUT_12_P$13") (pintype "output"))
    )
    (net (code "27") (name "FLAG_F5") (class "Default")
      (node (ref "CMP17") (pin "P$14") (pinfunction "OUT_13_P$14") (pintype "output"))
    )
    (net (code "28") (name "FLAG_F6") (class "Default")
      (node (ref "CMP17") (pin "P$15") (pinfunction "OUT_14_P$15") (pintype "output"))
    )
    (net (code "29") (name "FLAG_I") (class "Default")
      (node (ref "CMP17") (pin "P$1") (pinfunction "OUT_0_P$1") (pintype "output"))
    )
    (net (code "30") (name "FLAG_N") (class "Default")
      (node (ref "CMP17") (pin "P$2") (pinfunction "OUT_1_P$2") (pintype "output"))
    )
    (net (code "31") (name "FLAG_V") (class "Default")
      (node (ref "CMP17") (pin "P$4") (pinfunction "OUT_3_P$4") (pintype "output"))
    )
    (net (code "32") (name "FLAG_X") (class "Default")
      (node (ref "CMP17") (pin "P$5") (pinfunction "OUT_4_P$5") (pintype "output"))
      (node (ref "CMP7") (pin "P$2") (pinfunction "A1_P$2") (pintype "input"))
      (node (ref "CMP8") (pin "P$1") (pinfunction "A0_P$1") (pintype "input"))
    )
    (net (code "33") (name "FLAG_Z") (class "Default")
      (node (ref "CMP17") (pin "P$3") (pinfunction "OUT_2_P$3") (pintype "output"))
    )
    (net (code "34") (name "H_COUNT_IS_15") (class "Default")
      (node (ref "CMP57") (pin "P$3") (pinfunction "OUT_2_P$3") (pintype "output"))
      (node (ref "CMP79") (pin "P$9") (pinfunction "IN_8_P$9") (pintype "input"))
    )
    (net (code "35") (name "INSTR_0") (class "Default")
      (node (ref "CMP15") (pin "P$1") (pinfunction "OUT_0_P$1") (pintype "output"))
    )
    (net (code "36") (name "INSTR_0_N") (class "Default")
      (node (ref "CMP15") (pin "P$9") (pinfunction "OUT_8_P$9") (pintype "output"))
    )
    (net (code "37") (name "INSTR_1") (class "Default")
      (node (ref "CMP15") (pin "P$2") (pinfunction "OUT_1_P$2") (pintype "output"))
    )
    (net (code "38") (name "INSTR_1_N") (class "Default")
      (node (ref "CMP15") (pin "P$10") (pinfunction "OUT_9_P$10") (pintype "output"))
    )
    (net (code "39") (name "INSTR_2") (class "Default")
      (node (ref "CMP15") (pin "P$3") (pinfunction "OUT_2_P$3") (pintype "output"))
    )
    (net (code "40") (name "INSTR_2_N") (class "Default")
      (node (ref "CMP15") (pin "P$11") (pinfunction "OUT_10_P$11") (pintype "output"))
      (node (ref "CMP4") (pin "P$2") (pinfunction "A1_P$2") (pintype "input"))
      (node (ref "CMP6") (pin "P$1") (pinfunction "1_P$1") (pintype "input"))
    )
    (net (code "41") (name "INSTR_3") (class "Default")
      (node (ref "CMP1") (pin "P$1") (pinfunction "1_P$1") (pintype "input"))
      (node (ref "CMP15") (pin "P$4") (pinfunction "OUT_3_P$4") (pintype "output"))
      (node (ref "CMP4") (pin "P$1") (pinfunction "A2_P$1") (pintype "input"))
    )
    (net (code "42") (name "INSTR_3_N") (class "Default")
      (node (ref "CMP15") (pin "P$12") (pinfunction "OUT_11_P$12") (pintype "output"))
    )
    (net (code "43") (name "INSTR_4") (class "Default")
      (node (ref "CMP15") (pin "P$5") (pinfunction "OUT_4_P$5") (pintype "output"))
    )
    (net (code "44") (name "INSTR_4_N") (class "Default")
      (node (ref "CMP15") (pin "P$13") (pinfunction "OUT_12_P$13") (pintype "output"))
    )
    (net (code "45") (name "INSTR_5") (class "Default")
      (node (ref "CMP15") (pin "P$6") (pinfunction "OUT_5_P$6") (pintype "output"))
    )
    (net (code "46") (name "INSTR_5_N") (class "Default")
      (node (ref "CMP15") (pin "P$14") (pinfunction "OUT_13_P$14") (pintype "output"))
    )
    (net (code "47") (name "INSTR_6") (class "Default")
      (node (ref "CMP15") (pin "P$7") (pinfunction "OUT_6_P$7") (pintype "output"))
    )
    (net (code "48") (name "INSTR_6_N") (class "Default")
      (node (ref "CMP15") (pin "P$15") (pinfunction "OUT_14_P$15") (pintype "output"))
    )
    (net (code "49") (name "INSTR_7") (class "Default")
      (node (ref "CMP15") (pin "P$8") (pinfunction "OUT_7_P$8") (pintype "output"))
    )
    (net (code "50") (name "INSTR_7_N") (class "Default")
      (node (ref "CMP15") (pin "P$16") (pinfunction "OUT_15_P$16") (pintype "output"))
    )
    (net (code "51") (name "IS_END") (class "Default")
      (node (ref "CMP57") (pin "P$11") (pinfunction "OUT_10_P$11") (pintype "output"))
    )
    (net (code "52") (name "IS_END_N") (class "Default")
      (node (ref "CMP57") (pin "P$12") (pinfunction "OUT_11_P$12") (pintype "output"))
      (node (ref "CMP95") (pin "P$14") (pinfunction "IN_13_P$14") (pintype "input"))
    )
    (net (code "53") (name "IS_SIMPLE_DATA_TRANSFER") (class "Default")
      (node (ref "CMP57") (pin "P$13") (pinfunction "OUT_12_P$13") (pintype "output"))
    )
    (net (code "54") (name "K_BIT_0") (class "Default")
      (node (ref "CMP6") (pin "OUT_M") (pinfunction "N_OUT_M") (pintype "output"))
      (node (ref "CMP8") (pin "P$3") (pinfunction "B0_P$3") (pintype "input"))
    )
    (net (code "55") (name "K_BIT_1") (class "Default")
      (node (ref "CMP5") (pin "OUT_P") (pinfunction "P_OUT_P") (pintype "output"))
      (node (ref "CMP7") (pin "P$3") (pinfunction "B0_P$3") (pintype "input"))
    )
    (net (code "56") (name "K_MSBS") (class "Default")
      (node (ref "CMP1") (pin "OUT_P") (pinfunction "P_OUT_P") (pintype "output"))
      (node (ref "CMP93") (pin "P$9") (pinfunction "IN_8_P$9") (pintype "input"))
    )
    (net (code "57") (name "K_NOT_P1") (class "Default")
      (node (ref "CMP4") (pin "OUT_P") (pinfunction "P_OUT_P") (pintype "output"))
      (node (ref "CMP5") (pin "P$1") (pinfunction "1_P$1") (pintype "input"))
    )
    (net (code "58") (name "K_VALUE_0") (class "Default")
      (node (ref "CMP8") (pin "OUT_P") (pinfunction "P_OUT_P") (pintype "output"))
      (node (ref "CMP93") (pin "P$7") (pinfunction "IN_6_P$7") (pintype "input"))
    )
    (net (code "59") (name "K_VALUE_1") (class "Default")
      (node (ref "CMP7") (pin "OUT_P") (pinfunction "P_OUT_P") (pintype "output"))
      (node (ref "CMP93") (pin "P$8") (pinfunction "IN_7_P$8") (pintype "input"))
    )
    (net (code "60") (name "LDI_X_STATE_0_BYTE_1_WORD") (class "Default")
      (node (ref "CMP57") (pin "P$9") (pinfunction "OUT_8_P$9") (pintype "output"))
      (node (ref "CMP79") (pin "P$2") (pinfunction "IN_1_P$2") (pintype "input"))
    )
    (net (code "61") (name "LOAD_WEIGHT") (class "Default")
      (node (ref "CMP57") (pin "P$5") (pinfunction "OUT_4_P$5") (pintype "output"))
      (node (ref "CMP79") (pin "P$4") (pinfunction "IN_3_P$4") (pintype "input"))
      (node (ref "CMP99") (pin "P$14") (pinfunction "IN_13_P$14") (pintype "input"))
    )
    (net (code "62") (name "NEXT_VC_MUX_CLEAR__MISC_OPTIONS") (class "Default")
      (node (ref "CMP14") (pin "OUT_P") (pinfunction "P_OUT_P") (pintype "output"))
      (node (ref "CMP56") (pin "P$6") (pinfunction "IN_5_P$6") (pintype "input"))
    )
    (net (code "63") (name "Net-(CMP14-0)") (class "Default")
      (node (ref "CMP14") (pin "1") (pinfunction "0_1") (pintype "input"))
      (node (ref "CMP14") (pin "2") (pinfunction "1_2") (pintype "input"))
    )
    (net (code "64") (name "Net-(CMP79-IN_12)") (class "Default")
      (node (ref "CMP79") (pin "P$13") (pinfunction "IN_12_P$13") (pintype "input"))
      (node (ref "CMP79") (pin "P$14") (pinfunction "IN_13_P$14") (pintype "input"))
      (node (ref "CMP79") (pin "P$15") (pinfunction "IN_14_P$15") (pintype "input"))
      (node (ref "CMP79") (pin "P$16") (pinfunction "IN_15_P$16") (pintype "input"))
    )
    (net (code "65") (name "Net-(CMP93-IN_13)") (class "Default")
      (node (ref "CMP93") (pin "P$14") (pinfunction "IN_13_P$14") (pintype "input"))
      (node (ref "CMP93") (pin "P$15") (pinfunction "IN_14_P$15") (pintype "input"))
      (node (ref "CMP93") (pin "P$16") (pinfunction "IN_15_P$16") (pintype "input"))
    )
    (net (code "66") (name "OPCODE_IS_ABS") (class "Default")
      (node (ref "CMP47") (pin "P$4") (pinfunction "OUT_3_P$4") (pintype "output"))
      (node (ref "CMP56") (pin "P$13") (pinfunction "IN_12_P$13") (pintype "input"))
      (node (ref "CMP87") (pin "P$14") (pinfunction "IN_13_P$14") (pintype "input"))
    )
    (net (code "67") (name "OPCODE_IS_ABSOLUTE_GROUP") (class "Default")
      (node (ref "CMP2") (pin "P$5") (pinfunction "OUT_4_P$5") (pintype "output"))
    )
    (net (code "68") (name "OPCODE_IS_ADDQ_GROUP") (class "Default")
      (node (ref "CMP1") (pin "P$2") (pinfunction "2_P$2") (pintype "input"))
      (node (ref "CMP12") (pin "P$1") (pinfunction "A2_P$1") (pintype "input"))
      (node (ref "CMP2") (pin "P$11") (pinfunction "OUT_10_P$11") (pintype "output"))
      (node (ref "CMP5") (pin "P$2") (pinfunction "2_P$2") (pintype "input"))
      (node (ref "CMP6") (pin "P$2") (pinfunction "2_P$2") (pintype "input"))
      (node (ref "CMP93") (pin "P$6") (pinfunction "IN_5_P$6") (pintype "input"))
    )
    (net (code "69") (name "OPCODE_IS_ADDX") (class "Default")
      (node (ref "CMP35") (pin "P$3") (pinfunction "OUT_2_P$3") (pintype "output"))
      (node (ref "CMP87") (pin "P$12") (pinfunction "IN_11_P$12") (pintype "input"))
      (node (ref "CMP95") (pin "P$3") (pinfunction "IN_2_P$3") (pintype "input"))
    )
    (net (code "70") (name "OPCODE_IS_ADD_ADDQ") (class "Default")
      (node (ref "CMP12") (pin "OUT_P") (pinfunction "P_OUT_P") (pintype "output"))
      (node (ref "CMP56") (pin "P$9") (pinfunction "IN_8_P$9") (pintype "input"))
    )
    (net (code "71") (name "OPCODE_IS_ADD_GROUP") (class "Default")
      (node (ref "CMP12") (pin "P$2") (pinfunction "A1_P$2") (pintype "input"))
      (node (ref "CMP2") (pin "P$12") (pinfunction "OUT_11_P$12") (pintype "output"))
      (node (ref "CMP87") (pin "P$9") (pinfunction "IN_8_P$9") (pintype "input"))
    )
    (net (code "72") (name "OPCODE_IS_ADD_SP") (class "Default")
      (node (ref "CMP18") (pin "P$2") (pinfunction "2_P$2") (pintype "input"))
      (node (ref "CMP35") (pin "P$10") (pinfunction "OUT_9_P$10") (pintype "output"))
    )
    (net (code "73") (name "OPCODE_IS_ADD_SP_STATE_2") (class "Default")
      (node (ref "CMP18") (pin "OUT_P") (pinfunction "P_OUT_P") (pintype "output"))
      (node (ref "CMP91") (pin "P$15") (pinfunction "IN_14_P$15") (pintype "input"))
      (node (ref "CMP95") (pin "P$8") (pinfunction "IN_7_P$8") (pintype "input"))
    )
    (net (code "74") (name "OPCODE_IS_ANDI_PS") (class "Default")
      (node (ref "CMP35") (pin "P$12") (pinfunction "OUT_11_P$12") (pintype "output"))
      (node (ref "CMP56") (pin "P$4") (pinfunction "IN_3_P$4") (pintype "input"))
    )
    (net (code "75") (name "OPCODE_IS_AND_GROUP") (class "Default")
      (node (ref "CMP2") (pin "P$15") (pinfunction "OUT_14_P$15") (pintype "output"))
      (node (ref "CMP87") (pin "P$8") (pinfunction "IN_7_P$8") (pintype "input"))
    )
    (net (code "76") (name "OPCODE_IS_BIT_XX") (class "Default")
      (node (ref "CMP3") (pin "P$3") (pinfunction "OUT_2_P$3") (pintype "output"))
      (node (ref "CMP79") (pin "P$5") (pinfunction "IN_4_P$5") (pintype "input"))
      (node (ref "CMP80") (pin "P$3") (pinfunction "3_P$3") (pintype "input"))
      (node (ref "CMP87") (pin "P$5") (pinfunction "IN_4_P$5") (pintype "input"))
    )
    (net (code "77") (name "OPCODE_IS_BIT_XX_N") (class "Default")
      (node (ref "CMP3") (pin "P$4") (pinfunction "OUT_3_P$4") (pintype "output"))
      (node (ref "CMP93") (pin "P$2") (pinfunction "IN_1_P$2") (pintype "input"))
    )
    (net (code "78") (name "OPCODE_IS_BRANCH_GROUP") (class "Default")
      (node (ref "CMP19") (pin "P$2") (pinfunction "2_P$2") (pintype "input"))
      (node (ref "CMP2") (pin "P$3") (pinfunction "OUT_2_P$3") (pintype "output"))
      (node (ref "CMP56") (pin "P$1") (pinfunction "IN_0_P$1") (pintype "input"))
    )
    (net (code "79") (name "OPCODE_IS_BXX_STATE_2") (class "Default")
      (node (ref "CMP19") (pin "OUT_P") (pinfunction "P_OUT_P") (pintype "output"))
      (node (ref "CMP87") (pin "P$1") (pinfunction "IN_0_P$1") (pintype "input"))
    )
    (net (code "80") (name "OPCODE_IS_CMP") (class "Default")
      (node (ref "CMP103") (pin "P$2") (pinfunction "A1_P$2") (pintype "input"))
      (node (ref "CMP47") (pin "P$3") (pinfunction "OUT_2_P$3") (pintype "output"))
      (node (ref "CMP56") (pin "P$8") (pinfunction "IN_7_P$8") (pintype "input"))
      (node (ref "CMP93") (pin "P$1") (pinfunction "IN_0_P$1") (pintype "input"))
    )
    (net (code "81") (name "OPCODE_IS_CMP_GROUP") (class "Default")
      (node (ref "CMP2") (pin "P$9") (pinfunction "OUT_8_P$9") (pintype "output"))
      (node (ref "CMP93") (pin "P$10") (pinfunction "IN_9_P$10") (pintype "input"))
    )
    (net (code "82") (name "OPCODE_IS_DIV") (class "Default")
      (node (ref "CMP35") (pin "P$4") (pinfunction "OUT_3_P$4") (pintype "output"))
      (node (ref "CMP41") (pin "P$2") (pinfunction "2_P$2") (pintype "input"))
      (node (ref "CMP87") (pin "P$15") (pinfunction "IN_14_P$15") (pintype "input"))
      (node (ref "CMP99") (pin "P$6") (pinfunction "IN_5_P$6") (pintype "input"))
    )
    (net (code "83") (name "OPCODE_IS_DIVS") (class "Default")
      (node (ref "CMP35") (pin "P$5") (pinfunction "OUT_4_P$5") (pintype "output"))
      (node (ref "CMP42") (pin "P$2") (pinfunction "2_P$2") (pintype "input"))
      (node (ref "CMP68") (pin "P$2") (pinfunction "2_P$2") (pintype "input"))
    )
    (net (code "84") (name "OPCODE_IS_DIVS_STATE_0") (class "Default")
      (node (ref "CMP42") (pin "OUT_P") (pinfunction "P_OUT_P") (pintype "output"))
      (node (ref "CMP91") (pin "P$2") (pinfunction "IN_1_P$2") (pintype "input"))
      (node (ref "CMP95") (pin "P$16") (pinfunction "IN_15_P$16") (pintype "input"))
    )
    (net (code "85") (name "OPCODE_IS_DIV_STATE_0") (class "Default")
      (node (ref "CMP41") (pin "OUT_P") (pinfunction "P_OUT_P") (pintype "output"))
      (node (ref "CMP91") (pin "P$7") (pinfunction "IN_6_P$7") (pintype "input"))
      (node (ref "CMP99") (pin "P$10") (pinfunction "IN_9_P$10") (pintype "input"))
    )
    (net (code "86") (name "OPCODE_IS_INDIRECT_GROUP") (class "Default")
      (node (ref "CMP2") (pin "P$8") (pinfunction "OUT_7_P$8") (pintype "output"))
    )
    (net (code "87") (name "OPCODE_IS_INDIRECT_POSTINC") (class "Default")
      (node (ref "CMP2") (pin "P$1") (pinfunction "OUT_0_P$1") (pintype "output"))
      (node (ref "CMP91") (pin "P$9") (pinfunction "IN_8_P$9") (pintype "input"))
      (node (ref "CMP99") (pin "P$1") (pinfunction "IN_0_P$1") (pintype "input"))
    )
    (net (code "88") (name "OPCODE_IS_INV") (class "Default")
      (node (ref "CMP47") (pin "P$8") (pinfunction "OUT_7_P$8") (pintype "output"))
      (node (ref "CMP93") (pin "P$3") (pinfunction "IN_2_P$3") (pintype "input"))
    )
    (net (code "89") (name "OPCODE_IS_JMP_ABS") (class "Default")
      (node (ref "CMP35") (pin "P$13") (pinfunction "OUT_12_P$13") (pintype "output"))
    )
    (net (code "90") (name "OPCODE_IS_JMP_R0") (class "Default")
      (node (ref "CMP35") (pin "P$14") (pinfunction "OUT_13_P$14") (pintype "output"))
      (node (ref "CMP91") (pin "P$11") (pinfunction "IN_10_P$11") (pintype "input"))
    )
    (net (code "91") (name "OPCODE_IS_JSR_ABS") (class "Default")
      (node (ref "CMP3") (pin "P$10") (pinfunction "OUT_9_P$10") (pintype "output"))
      (node (ref "CMP91") (pin "P$14") (pinfunction "IN_13_P$14") (pintype "input"))
      (node (ref "CMP95") (pin "P$15") (pinfunction "IN_14_P$15") (pintype "input"))
    )
    (net (code "92") (name "OPCODE_IS_JSR_R0") (class "Default")
      (node (ref "CMP3") (pin "P$11") (pinfunction "OUT_10_P$11") (pintype "output"))
      (node (ref "CMP91") (pin "P$5") (pinfunction "IN_4_P$5") (pintype "input"))
      (node (ref "CMP99") (pin "P$3") (pinfunction "IN_2_P$3") (pintype "input"))
    )
    (net (code "93") (name "OPCODE_IS_JSR_X") (class "Default")
      (node (ref "CMP21") (pin "P$1") (pinfunction "1_P$1") (pintype "input"))
      (node (ref "CMP57") (pin "P$10") (pinfunction "OUT_9_P$10") (pintype "output"))
    )
    (net (code "94") (name "OPCODE_IS_JSR_X_STATE_7") (class "Default")
      (node (ref "CMP21") (pin "OUT_P") (pinfunction "P_OUT_P") (pintype "output"))
      (node (ref "CMP91") (pin "P$8") (pinfunction "IN_7_P$8") (pintype "input"))
    )
    (net (code "95") (name "OPCODE_IS_LDI_X") (class "Default")
      (node (ref "CMP14") (pin "6") (pinfunction "5_6") (pintype "input"))
      (node (ref "CMP3") (pin "P$1") (pinfunction "OUT_0_P$1") (pintype "output"))
      (node (ref "CMP99") (pin "P$11") (pinfunction "IN_10_P$11") (pintype "input"))
    )
    (net (code "96") (name "OPCODE_IS_LD_ST") (class "Default")
      (node (ref "CMP10") (pin "P$2") (pinfunction "2_P$2") (pintype "input"))
      (node (ref "CMP57") (pin "P$8") (pinfunction "OUT_7_P$8") (pintype "output"))
      (node (ref "CMP9") (pin "P$1") (pinfunction "1_P$1") (pintype "input"))
      (node (ref "CMP99") (pin "P$4") (pinfunction "IN_3_P$4") (pintype "input"))
    )
    (net (code "97") (name "OPCODE_IS_LD_ST_STATE_0") (class "Default")
      (node (ref "CMP56") (pin "P$16") (pinfunction "IN_15_P$16") (pintype "input"))
      (node (ref "CMP9") (pin "OUT_P") (pinfunction "P_OUT_P") (pintype "output"))
    )
    (net (code "98") (name "OPCODE_IS_LD_ST_STATE_5") (class "Default")
      (node (ref "CMP10") (pin "OUT_P") (pinfunction "P_OUT_P") (pintype "output"))
      (node (ref "CMP79") (pin "P$1") (pinfunction "IN_0_P$1") (pintype "input"))
    )
    (net (code "99") (name "OPCODE_IS_LOGIC_GROUP") (class "Default")
      (node (ref "CMP2") (pin "P$2") (pinfunction "OUT_1_P$2") (pintype "output"))
      (node (ref "CMP87") (pin "P$3") (pinfunction "IN_2_P$3") (pintype "input"))
    )
    (net (code "100") (name "OPCODE_IS_MOVER") (class "Default")
      (node (ref "CMP47") (pin "P$10") (pinfunction "OUT_9_P$10") (pintype "output"))
      (node (ref "CMP93") (pin "P$11") (pinfunction "IN_10_P$11") (pintype "input"))
    )
    (net (code "101") (name "OPCODE_IS_MOVE_R0_SP") (class "Default")
      (node (ref "CMP16") (pin "P$2") (pinfunction "2_P$2") (pintype "input"))
      (node (ref "CMP35") (pin "P$16") (pinfunction "OUT_15_P$16") (pintype "output"))
    )
    (net (code "102") (name "OPCODE_IS_MOVE_R0_SP_STATE_0") (class "Default")
      (node (ref "CMP16") (pin "OUT_P") (pinfunction "P_OUT_P") (pintype "output"))
      (node (ref "CMP91") (pin "P$12") (pinfunction "IN_11_P$12") (pintype "input"))
      (node (ref "CMP95") (pin "P$9") (pinfunction "IN_8_P$9") (pintype "input"))
    )
    (net (code "103") (name "OPCODE_IS_MOVE_SP_R0") (class "Default")
      (node (ref "CMP35") (pin "P$15") (pinfunction "OUT_14_P$15") (pintype "output"))
      (node (ref "CMP91") (pin "P$10") (pinfunction "IN_9_P$10") (pintype "input"))
    )
    (net (code "104") (name "OPCODE_IS_MUL") (class "Default")
      (node (ref "CMP35") (pin "P$7") (pinfunction "OUT_6_P$7") (pintype "output"))
      (node (ref "CMP95") (pin "P$10") (pinfunction "IN_9_P$10") (pintype "input"))
    )
    (net (code "105") (name "OPCODE_IS_MULS") (class "Default")
      (node (ref "CMP35") (pin "P$8") (pinfunction "OUT_7_P$8") (pintype "output"))
      (node (ref "CMP87") (pin "P$13") (pinfunction "IN_12_P$13") (pintype "input"))
      (node (ref "CMP95") (pin "P$5") (pinfunction "IN_4_P$5") (pintype "input"))
    )
    (net (code "106") (name "OPCODE_IS_MUL_N") (class "Default")
      (node (ref "CMP35") (pin "P$6") (pinfunction "OUT_5_P$6") (pintype "output"))
      (node (ref "CMP7") (pin "P$4") (pinfunction "B1_P$4") (pintype "input"))
      (node (ref "CMP8") (pin "P$4") (pinfunction "B1_P$4") (pintype "input"))
      (node (ref "CMP91") (pin "P$13") (pinfunction "IN_12_P$13") (pintype "input"))
    )
    (net (code "107") (name "OPCODE_IS_MUL_SQRT_DIV") (class "Default")
      (node (ref "CMP14") (pin "4") (pinfunction "3_4") (pintype "input"))
      (node (ref "CMP47") (pin "P$1") (pinfunction "OUT_0_P$1") (pintype "output"))
      (node (ref "CMP56") (pin "P$5") (pinfunction "IN_4_P$5") (pintype "input"))
    )
    (net (code "108") (name "OPCODE_IS_NEG") (class "Default")
      (node (ref "CMP47") (pin "P$6") (pinfunction "OUT_5_P$6") (pintype "output"))
      (node (ref "CMP56") (pin "P$7") (pinfunction "IN_6_P$7") (pintype "input"))
      (node (ref "CMP87") (pin "P$4") (pinfunction "IN_3_P$4") (pintype "input"))
    )
    (net (code "109") (name "OPCODE_IS_NEGX") (class "Default")
      (node (ref "CMP35") (pin "P$1") (pinfunction "OUT_0_P$1") (pintype "output"))
      (node (ref "CMP87") (pin "P$10") (pinfunction "IN_9_P$10") (pintype "input"))
      (node (ref "CMP95") (pin "P$6") (pinfunction "IN_5_P$6") (pintype "input"))
    )
    (net (code "110") (name "OPCODE_IS_OR") (class "Default")
      (node (ref "CMP47") (pin "P$7") (pinfunction "OUT_6_P$7") (pintype "output"))
      (node (ref "CMP87") (pin "P$7") (pinfunction "IN_6_P$7") (pintype "input"))
    )
    (net (code "111") (name "OPCODE_IS_ORI_PS") (class "Default")
      (node (ref "CMP35") (pin "P$11") (pinfunction "OUT_10_P$11") (pintype "output"))
      (node (ref "CMP56") (pin "P$3") (pinfunction "IN_2_P$3") (pintype "input"))
    )
    (net (code "112") (name "OPCODE_IS_OR_GROUP") (class "Default")
      (node (ref "CMP2") (pin "P$13") (pinfunction "OUT_12_P$13") (pintype "output"))
      (node (ref "CMP93") (pin "P$12") (pinfunction "IN_11_P$12") (pintype "input"))
    )
    (net (code "113") (name "OPCODE_IS_POP_PS") (class "Default")
      (node (ref "CMP3") (pin "P$16") (pinfunction "OUT_15_P$16") (pintype "output"))
      (node (ref "CMP37") (pin "4") (pinfunction "3_4") (pintype "input"))
      (node (ref "CMP56") (pin "P$2") (pinfunction "IN_1_P$2") (pintype "input"))
      (node (ref "CMP99") (pin "P$5") (pinfunction "IN_4_P$5") (pintype "input"))
    )
    (net (code "114") (name "OPCODE_IS_POP_RA") (class "Default")
      (node (ref "CMP14") (pin "8") (pinfunction "7_8") (pintype "input"))
      (node (ref "CMP37") (pin "2") (pinfunction "1_2") (pintype "input"))
      (node (ref "CMP47") (pin "P$15") (pinfunction "OUT_14_P$15") (pintype "output"))
    )
    (net (code "115") (name "OPCODE_IS_POSTINC_GROUP") (class "Default")
      (node (ref "CMP2") (pin "P$7") (pinfunction "OUT_6_P$7") (pintype "output"))
      (node (ref "CMP99") (pin "P$15") (pinfunction "IN_14_P$15") (pintype "input"))
    )
    (net (code "116") (name "OPCODE_IS_PUSH_PS") (class "Default")
      (node (ref "CMP3") (pin "P$13") (pinfunction "OUT_12_P$13") (pintype "output"))
      (node (ref "CMP91") (pin "P$3") (pinfunction "IN_2_P$3") (pintype "input"))
    )
    (net (code "117") (name "OPCODE_IS_PUSH_RA") (class "Default")
      (node (ref "CMP14") (pin "3") (pinfunction "2_3") (pintype "input"))
      (node (ref "CMP47") (pin "P$16") (pinfunction "OUT_15_P$16") (pintype "output"))
      (node (ref "CMP91") (pin "P$4") (pinfunction "IN_3_P$4") (pintype "input"))
    )
    (net (code "118") (name "OPCODE_IS_RET") (class "Default")
      (node (ref "CMP3") (pin "P$15") (pinfunction "OUT_14_P$15") (pintype "output"))
      (node (ref "CMP37") (pin "3") (pinfunction "2_3") (pintype "input"))
    )
    (net (code "119") (name "OPCODE_IS_RETI") (class "Default")
      (node (ref "CMP3") (pin "P$14") (pinfunction "OUT_13_P$14") (pintype "output"))
      (node (ref "CMP37") (pin "1") (pinfunction "0_1") (pintype "input"))
    )
    (net (code "120") (name "OPCODE_IS_SHIFT_BIT") (class "Default")
      (node (ref "CMP3") (pin "P$5") (pinfunction "OUT_4_P$5") (pintype "output"))
      (node (ref "CMP95") (pin "P$4") (pinfunction "IN_3_P$4") (pintype "input"))
    )
    (net (code "121") (name "OPCODE_IS_SHIFT_XX") (class "Default")
      (node (ref "CMP14") (pin "7") (pinfunction "6_7") (pintype "input"))
      (node (ref "CMP3") (pin "P$2") (pinfunction "OUT_1_P$2") (pintype "output"))
      (node (ref "CMP56") (pin "P$15") (pinfunction "IN_14_P$15") (pintype "input"))
      (node (ref "CMP87") (pin "P$2") (pinfunction "IN_1_P$2") (pintype "input"))
    )
    (net (code "122") (name "OPCODE_IS_SQRT") (class "Default")
      (node (ref "CMP35") (pin "P$9") (pinfunction "OUT_8_P$9") (pintype "output"))
      (node (ref "CMP87") (pin "P$16") (pinfunction "IN_15_P$16") (pintype "input"))
      (node (ref "CMP95") (pin "P$12") (pinfunction "IN_11_P$12") (pintype "input"))
    )
    (net (code "123") (name "OPCODE_IS_STACK_GROUP") (class "Default")
      (node (ref "CMP2") (pin "P$4") (pinfunction "OUT_3_P$4") (pintype "output"))
      (node (ref "CMP93") (pin "P$5") (pinfunction "IN_4_P$5") (pintype "input"))
      (node (ref "CMP95") (pin "P$13") (pinfunction "IN_12_P$13") (pintype "input"))
    )
    (net (code "124") (name "OPCODE_IS_STACK_REL_GROUP") (class "Default")
      (node (ref "CMP2") (pin "P$6") (pinfunction "OUT_5_P$6") (pintype "output"))
      (node (ref "CMP20") (pin "P$1") (pinfunction "1_P$1") (pintype "input"))
    )
    (net (code "125") (name "OPCODE_IS_STACK_REL_STATE_2") (class "Default")
      (node (ref "CMP20") (pin "OUT_P") (pinfunction "P_OUT_P") (pintype "output"))
      (node (ref "CMP91") (pin "P$16") (pinfunction "IN_15_P$16") (pintype "input"))
      (node (ref "CMP95") (pin "P$11") (pinfunction "IN_10_P$11") (pintype "input"))
    )
    (net (code "126") (name "OPCODE_IS_SUB") (class "Default")
      (node (ref "CMP47") (pin "P$5") (pinfunction "OUT_4_P$5") (pintype "output"))
      (node (ref "CMP56") (pin "P$11") (pinfunction "IN_10_P$11") (pintype "input"))
      (node (ref "CMP87") (pin "P$6") (pinfunction "IN_5_P$6") (pintype "input"))
    )
    (net (code "127") (name "OPCODE_IS_SUBX") (class "Default")
      (node (ref "CMP35") (pin "P$2") (pinfunction "OUT_1_P$2") (pintype "output"))
      (node (ref "CMP87") (pin "P$11") (pinfunction "IN_10_P$11") (pintype "input"))
      (node (ref "CMP95") (pin "P$2") (pinfunction "IN_1_P$2") (pintype "input"))
    )
    (net (code "128") (name "OPCODE_IS_SUB_GROUP") (class "Default")
      (node (ref "CMP2") (pin "P$10") (pinfunction "OUT_9_P$10") (pintype "output"))
      (node (ref "CMP56") (pin "P$10") (pinfunction "IN_9_P$10") (pintype "input"))
      (node (ref "CMP93") (pin "P$4") (pinfunction "IN_3_P$4") (pintype "input"))
    )
    (net (code "129") (name "OPCODE_IS_SXT") (class "Default")
      (node (ref "CMP14") (pin "5") (pinfunction "4_5") (pintype "input"))
      (node (ref "CMP47") (pin "P$11") (pinfunction "OUT_10_P$11") (pintype "output"))
      (node (ref "CMP95") (pin "P$7") (pinfunction "IN_6_P$7") (pintype "input"))
    )
    (net (code "130") (name "OPCODE_IS_TEST") (class "Default")
      (node (ref "CMP103") (pin "P$1") (pinfunction "A2_P$1") (pintype "input"))
      (node (ref "CMP47") (pin "P$9") (pinfunction "OUT_8_P$9") (pintype "output"))
    )
    (net (code "131") (name "OPCODE_IS_TRAP") (class "Default")
      (node (ref "CMP3") (pin "P$12") (pinfunction "OUT_11_P$12") (pintype "output"))
      (node (ref "CMP56") (pin "P$14") (pinfunction "IN_13_P$14") (pintype "input"))
      (node (ref "CMP91") (pin "P$6") (pinfunction "IN_5_P$6") (pintype "input"))
      (node (ref "CMP99") (pin "P$2") (pinfunction "IN_1_P$2") (pintype "input"))
    )
    (net (code "132") (name "OPCODE_IS_XOR_GROUP") (class "Default")
      (node (ref "CMP2") (pin "P$14") (pinfunction "OUT_13_P$14") (pintype "output"))
      (node (ref "CMP93") (pin "P$13") (pinfunction "IN_12_P$13") (pintype "input"))
    )
    (net (code "133") (name "OPCODE_IS_X_ARITH") (class "Default")
      (node (ref "CMP47") (pin "P$2") (pinfunction "OUT_1_P$2") (pintype "output"))
      (node (ref "CMP56") (pin "P$12") (pinfunction "IN_11_P$12") (pintype "input"))
      (node (ref "CMP99") (pin "P$16") (pinfunction "IN_15_P$16") (pintype "input"))
    )
    (net (code "134") (name "SHIFTING_NOT_ROTATION") (class "Default")
      (node (ref "CMP11") (pin "OUT_P") (pinfunction "P_OUT_P") (pintype "output"))
      (node (ref "CMP79") (pin "P$7") (pinfunction "IN_6_P$7") (pintype "input"))
    )
    (net (code "135") (name "SHIFT_IS_SHIFTING") (class "Default")
      (node (ref "CMP11") (pin "P$1") (pinfunction "1_P$1") (pintype "input"))
      (node (ref "CMP57") (pin "P$4") (pinfunction "OUT_3_P$4") (pintype "output"))
      (node (ref "CMP79") (pin "P$3") (pinfunction "IN_2_P$3") (pintype "input"))
      (node (ref "CMP91") (pin "P$1") (pinfunction "IN_0_P$1") (pintype "input"))
      (node (ref "CMP99") (pin "P$8") (pinfunction "IN_7_P$8") (pintype "input"))
    )
    (net (code "136") (name "SHIFT_VAL_NON_ZERO") (class "Default")
      (node (ref "CMP57") (pin "P$1") (pinfunction "OUT_0_P$1") (pintype "output"))
    )
    (net (code "137") (name "SHIFT_VAL_NON_ZERO_N") (class "Default")
      (node (ref "CMP57") (pin "P$2") (pinfunction "OUT_1_P$2") (pintype "output"))
    )
    (net (code "138") (name "STATE_0") (class "Default")
      (node (ref "CMP13") (pin "P$1") (pinfunction "OUT_0_P$1") (pintype "output"))
      (node (ref "CMP16") (pin "P$1") (pinfunction "1_P$1") (pintype "input"))
      (node (ref "CMP41") (pin "P$1") (pinfunction "1_P$1") (pintype "input"))
      (node (ref "CMP42") (pin "P$1") (pinfunction "1_P$1") (pintype "input"))
      (node (ref "CMP9") (pin "P$2") (pinfunction "2_P$2") (pintype "input"))
    )
    (net (code "139") (name "STATE_1") (class "Default")
      (node (ref "CMP13") (pin "P$2") (pinfunction "OUT_1_P$2") (pintype "output"))
    )
    (net (code "140") (name "STATE_2") (class "Default")
      (node (ref "CMP13") (pin "P$3") (pinfunction "OUT_2_P$3") (pintype "output"))
      (node (ref "CMP18") (pin "P$1") (pinfunction "1_P$1") (pintype "input"))
      (node (ref "CMP19") (pin "P$1") (pinfunction "1_P$1") (pintype "input"))
      (node (ref "CMP20") (pin "P$2") (pinfunction "2_P$2") (pintype "input"))
    )
    (net (code "141") (name "STATE_3") (class "Default")
      (node (ref "CMP13") (pin "P$4") (pinfunction "OUT_3_P$4") (pintype "output"))
      (node (ref "CMP80") (pin "P$1") (pinfunction "1_P$1") (pintype "input"))
    )
    (net (code "142") (name "STATE_4") (class "Default")
      (node (ref "CMP13") (pin "P$5") (pinfunction "OUT_4_P$5") (pintype "output"))
    )
    (net (code "143") (name "STATE_5") (class "Default")
      (node (ref "CMP10") (pin "P$1") (pinfunction "1_P$1") (pintype "input"))
      (node (ref "CMP13") (pin "P$6") (pinfunction "OUT_5_P$6") (pintype "output"))
    )
    (net (code "144") (name "STATE_6") (class "Default")
      (node (ref "CMP13") (pin "P$7") (pinfunction "OUT_6_P$7") (pintype "output"))
    )
    (net (code "145") (name "STATE_7") (class "Default")
      (node (ref "CMP13") (pin "P$8") (pinfunction "OUT_7_P$8") (pintype "output"))
      (node (ref "CMP21") (pin "P$2") (pinfunction "2_P$2") (pintype "input"))
    )
    (net (code "146") (name "STATE_8") (class "Default")
      (node (ref "CMP13") (pin "P$9") (pinfunction "OUT_8_P$9") (pintype "output"))
    )
    (net (code "147") (name "STATE_9") (class "Default")
      (node (ref "CMP13") (pin "P$10") (pinfunction "OUT_9_P$10") (pintype "output"))
    )
    (net (code "148") (name "STATE_10") (class "Default")
      (node (ref "CMP13") (pin "P$11") (pinfunction "OUT_10_P$11") (pintype "output"))
    )
    (net (code "149") (name "STATE_11") (class "Default")
      (node (ref "CMP13") (pin "P$12") (pinfunction "OUT_11_P$12") (pintype "output"))
    )
    (net (code "150") (name "STATE_12") (class "Default")
      (node (ref "CMP13") (pin "P$13") (pinfunction "OUT_12_P$13") (pintype "output"))
    )
    (net (code "151") (name "STATE_13") (class "Default")
      (node (ref "CMP13") (pin "P$14") (pinfunction "OUT_13_P$14") (pintype "output"))
      (node (ref "CMP7") (pin "P$1") (pinfunction "A0_P$1") (pintype "input"))
    )
    (net (code "152") (name "STATE_14") (class "Default")
      (node (ref "CMP13") (pin "P$15") (pinfunction "OUT_14_P$15") (pintype "output"))
    )
    (net (code "153") (name "STATE_15") (class "Default")
      (node (ref "CMP13") (pin "P$16") (pinfunction "OUT_15_P$16") (pintype "output"))
    )
    (net (code "154") (name "TAKE_INTERRUPT") (class "Default")
      (node (ref "CMP57") (pin "P$7") (pinfunction "OUT_6_P$7") (pintype "output"))
      (node (ref "CMP79") (pin "P$12") (pinfunction "IN_11_P$12") (pintype "input"))
    )
    (net (code "155") (name "TRAP_STATE_7") (class "Default")
      (node (ref "CMP57") (pin "P$6") (pinfunction "OUT_5_P$6") (pintype "output"))
      (node (ref "CMP79") (pin "P$11") (pinfunction "IN_10_P$11") (pintype "input"))
    )
    (net (code "156") (name "WR_RN_USING_RA__BIT") (class "Default")
      (node (ref "CMP80") (pin "OUT_P") (pinfunction "P_OUT_P") (pintype "output"))
      (node (ref "CMP99") (pin "P$7") (pinfunction "IN_6_P$7") (pintype "input"))
    )
    (net (code "157") (name "WR_RN_USING_RA__REG_REG_EXCEPTIONS") (class "Default")
      (node (ref "CMP103") (pin "OUT_P") (pinfunction "P_OUT_P") (pintype "output"))
    )
    (net (code "158") (name "WR_RN_USING_RA__REG_REG_EXCEPTIONS_N") (class "Default")
      (node (ref "CMP103") (pin "OUT_M") (pinfunction "N_OUT_M") (pintype "output"))
      (node (ref "CMP99") (pin "P$12") (pinfunction "IN_11_P$12") (pintype "input"))
    )
    (net (code "159") (name "unconnected-(CMP1-N-PadOUT_M)") (class "Default")
      (node (ref "CMP1") (pin "OUT_M") (pinfunction "N_OUT_M") (pintype "output"))
    )
    (net (code "160") (name "unconnected-(CMP2-OUT_15-PadP$16)") (class "Default")
      (node (ref "CMP2") (pin "P$16") (pinfunction "OUT_15_P$16") (pintype "output"))
    )
    (net (code "161") (name "unconnected-(CMP2-PadINPUT)") (class "Default")
      (node (ref "CMP2") (pin "INPUT") (pinfunction "INPUT_INPUT") (pintype "input"))
    )
    (net (code "162") (name "unconnected-(CMP3-PadINPUT)") (class "Default")
      (node (ref "CMP3") (pin "INPUT") (pinfunction "INPUT_INPUT") (pintype "input"))
    )
    (net (code "163") (name "unconnected-(CMP4-N-PadOUT_M)") (class "Default")
      (node (ref "CMP4") (pin "OUT_M") (pinfunction "N_OUT_M") (pintype "output"))
    )
    (net (code "164") (name "unconnected-(CMP5-N-PadOUT_M)") (class "Default")
      (node (ref "CMP5") (pin "OUT_M") (pinfunction "N_OUT_M") (pintype "output"))
    )
    (net (code "165") (name "unconnected-(CMP6-P-PadOUT_P)") (class "Default")
      (node (ref "CMP6") (pin "OUT_P") (pinfunction "P_OUT_P") (pintype "output"))
    )
    (net (code "166") (name "unconnected-(CMP7-N-PadOUT_M)") (class "Default")
      (node (ref "CMP7") (pin "OUT_M") (pinfunction "N_OUT_M") (pintype "output"))
    )
    (net (code "167") (name "unconnected-(CMP8-N-PadOUT_M)") (class "Default")
      (node (ref "CMP8") (pin "OUT_M") (pinfunction "N_OUT_M") (pintype "output"))
    )
    (net (code "168") (name "unconnected-(CMP9-N-PadOUT_M)") (class "Default")
      (node (ref "CMP9") (pin "OUT_M") (pinfunction "N_OUT_M") (pintype "output"))
    )
    (net (code "169") (name "unconnected-(CMP10-N-PadOUT_M)") (class "Default")
      (node (ref "CMP10") (pin "OUT_M") (pinfunction "N_OUT_M") (pintype "output"))
    )
    (net (code "170") (name "unconnected-(CMP11-N-PadOUT_M)") (class "Default")
      (node (ref "CMP11") (pin "OUT_M") (pinfunction "N_OUT_M") (pintype "output"))
    )
    (net (code "171") (name "unconnected-(CMP12-N-PadOUT_M)") (class "Default")
      (node (ref "CMP12") (pin "OUT_M") (pinfunction "N_OUT_M") (pintype "output"))
    )
    (net (code "172") (name "unconnected-(CMP14-N-PadOUT_M)") (class "Default")
      (node (ref "CMP14") (pin "OUT_M") (pinfunction "N_OUT_M") (pintype "output"))
    )
    (net (code "173") (name "unconnected-(CMP16-N-PadOUT_M)") (class "Default")
      (node (ref "CMP16") (pin "OUT_M") (pinfunction "N_OUT_M") (pintype "output"))
    )
    (net (code "174") (name "unconnected-(CMP17-OUT_7-PadP$8)") (class "Default")
      (node (ref "CMP17") (pin "P$8") (pinfunction "OUT_7_P$8") (pintype "output"))
    )
    (net (code "175") (name "unconnected-(CMP17-OUT_15-PadP$16)") (class "Default")
      (node (ref "CMP17") (pin "P$16") (pinfunction "OUT_15_P$16") (pintype "output"))
    )
    (net (code "176") (name "unconnected-(CMP18-N-PadOUT_M)") (class "Default")
      (node (ref "CMP18") (pin "OUT_M") (pinfunction "N_OUT_M") (pintype "output"))
    )
    (net (code "177") (name "unconnected-(CMP19-N-PadOUT_M)") (class "Default")
      (node (ref "CMP19") (pin "OUT_M") (pinfunction "N_OUT_M") (pintype "output"))
    )
    (net (code "178") (name "unconnected-(CMP20-N-PadOUT_M)") (class "Default")
      (node (ref "CMP20") (pin "OUT_M") (pinfunction "N_OUT_M") (pintype "output"))
    )
    (net (code "179") (name "unconnected-(CMP21-N-PadOUT_M)") (class "Default")
      (node (ref "CMP21") (pin "OUT_M") (pinfunction "N_OUT_M") (pintype "output"))
    )
    (net (code "180") (name "unconnected-(CMP35-PadINPUT)") (class "Default")
      (node (ref "CMP35") (pin "INPUT") (pinfunction "INPUT_INPUT") (pintype "input"))
    )
    (net (code "181") (name "unconnected-(CMP37-N-PadOUT_M)") (class "Default")
      (node (ref "CMP37") (pin "OUT_M") (pinfunction "N_OUT_M") (pintype "output"))
    )
    (net (code "182") (name "unconnected-(CMP41-N-PadOUT_M)") (class "Default")
      (node (ref "CMP41") (pin "OUT_M") (pinfunction "N_OUT_M") (pintype "output"))
    )
    (net (code "183") (name "unconnected-(CMP42-N-PadOUT_M)") (class "Default")
      (node (ref "CMP42") (pin "OUT_M") (pinfunction "N_OUT_M") (pintype "output"))
    )
    (net (code "184") (name "unconnected-(CMP47-OUT_13-PadP$14)") (class "Default")
      (node (ref "CMP47") (pin "P$14") (pinfunction "OUT_13_P$14") (pintype "output"))
    )
    (net (code "185") (name "unconnected-(CMP47-PadINPUT)") (class "Default")
      (node (ref "CMP47") (pin "INPUT") (pinfunction "INPUT_INPUT") (pintype "input"))
    )
    (net (code "186") (name "unconnected-(CMP57-OUT_13-PadP$14)") (class "Default")
      (node (ref "CMP57") (pin "P$14") (pinfunction "OUT_13_P$14") (pintype "output"))
    )
    (net (code "187") (name "unconnected-(CMP57-OUT_14-PadP$15)") (class "Default")
      (node (ref "CMP57") (pin "P$15") (pinfunction "OUT_14_P$15") (pintype "output"))
    )
    (net (code "188") (name "unconnected-(CMP57-OUT_15-PadP$16)") (class "Default")
      (node (ref "CMP57") (pin "P$16") (pinfunction "OUT_15_P$16") (pintype "output"))
    )
    (net (code "189") (name "unconnected-(CMP57-PadINPUT)") (class "Default")
      (node (ref "CMP57") (pin "INPUT") (pinfunction "INPUT_INPUT") (pintype "input"))
    )
    (net (code "190") (name "unconnected-(CMP68-N-PadOUT_M)") (class "Default")
      (node (ref "CMP68") (pin "OUT_M") (pinfunction "N_OUT_M") (pintype "output"))
    )
    (net (code "191") (name "unconnected-(CMP80-M-PadOUT_M)") (class "Default")
      (node (ref "CMP80") (pin "OUT_M") (pinfunction "M_OUT_M") (pintype "output"))
    )
    (net (code "192") (name "unconnected-(CMP100-N-PadOUT_N)") (class "Default")
      (node (ref "CMP100") (pin "OUT_N") (pinfunction "N_OUT_N") (pintype "output"))
    )
  )
)
